# ISA_Sound_Card.net
KiCad netlist of a schematic drawn in EAGLE
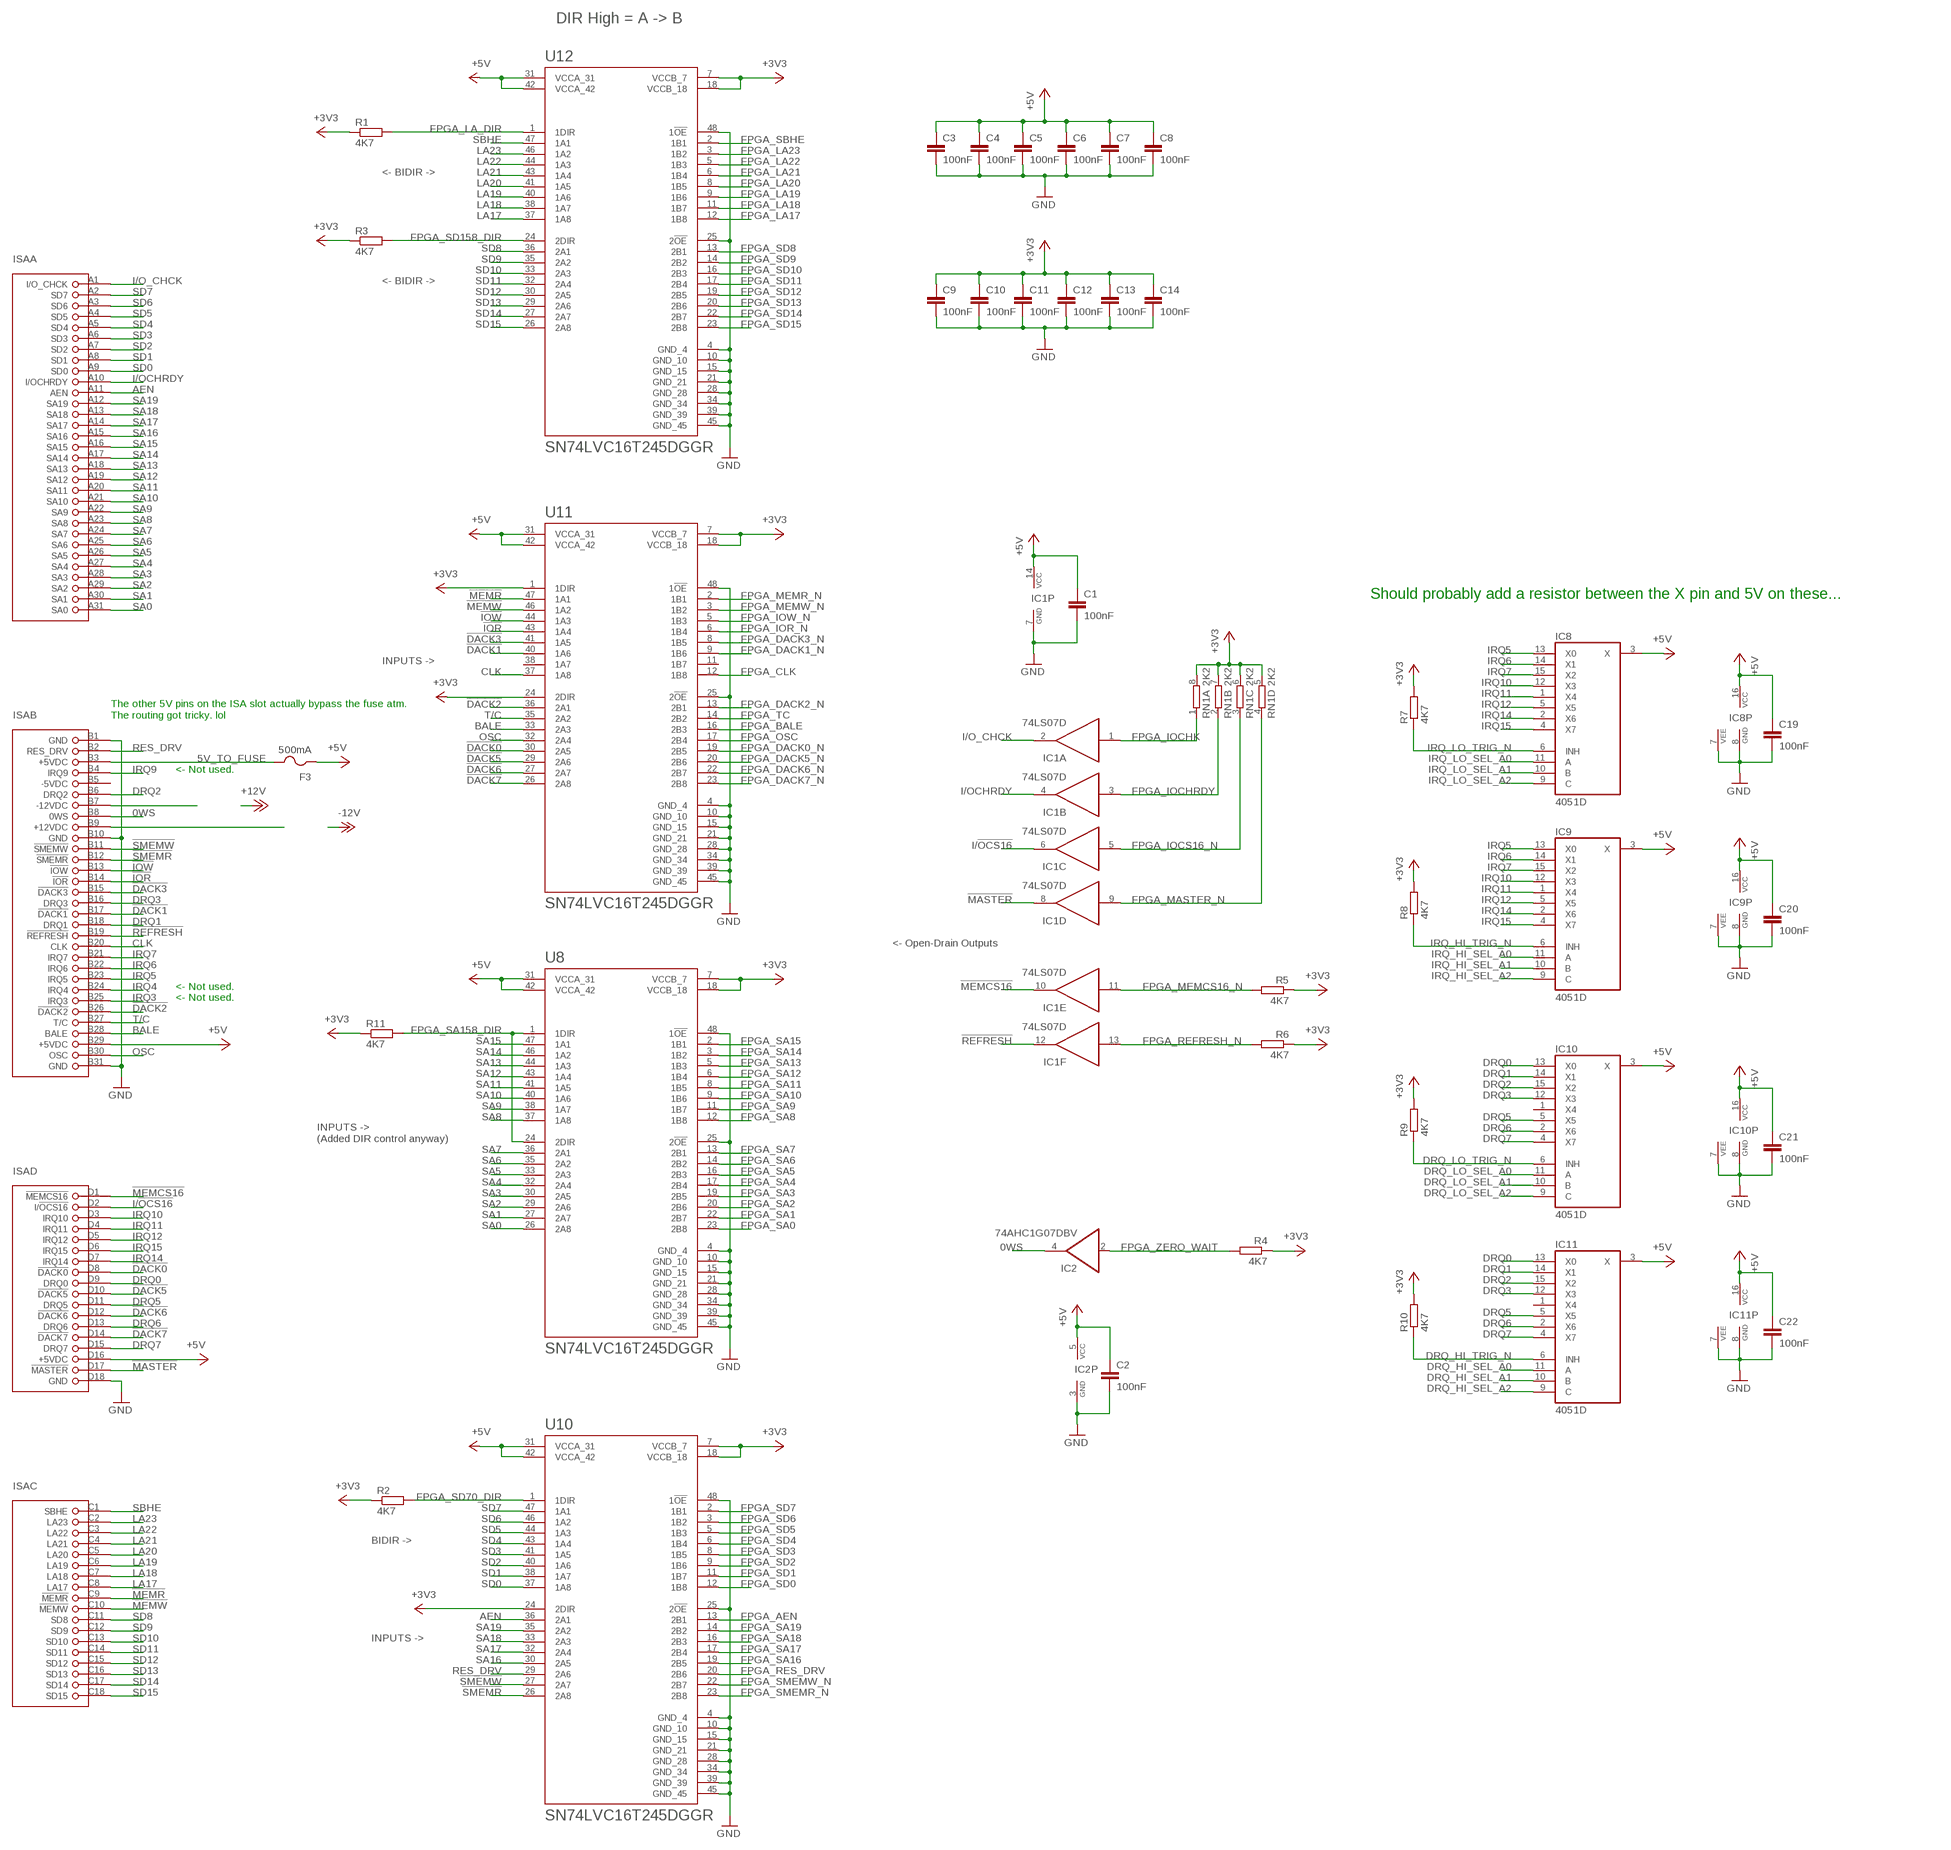
[diagram p0: schematic, sheet 1]
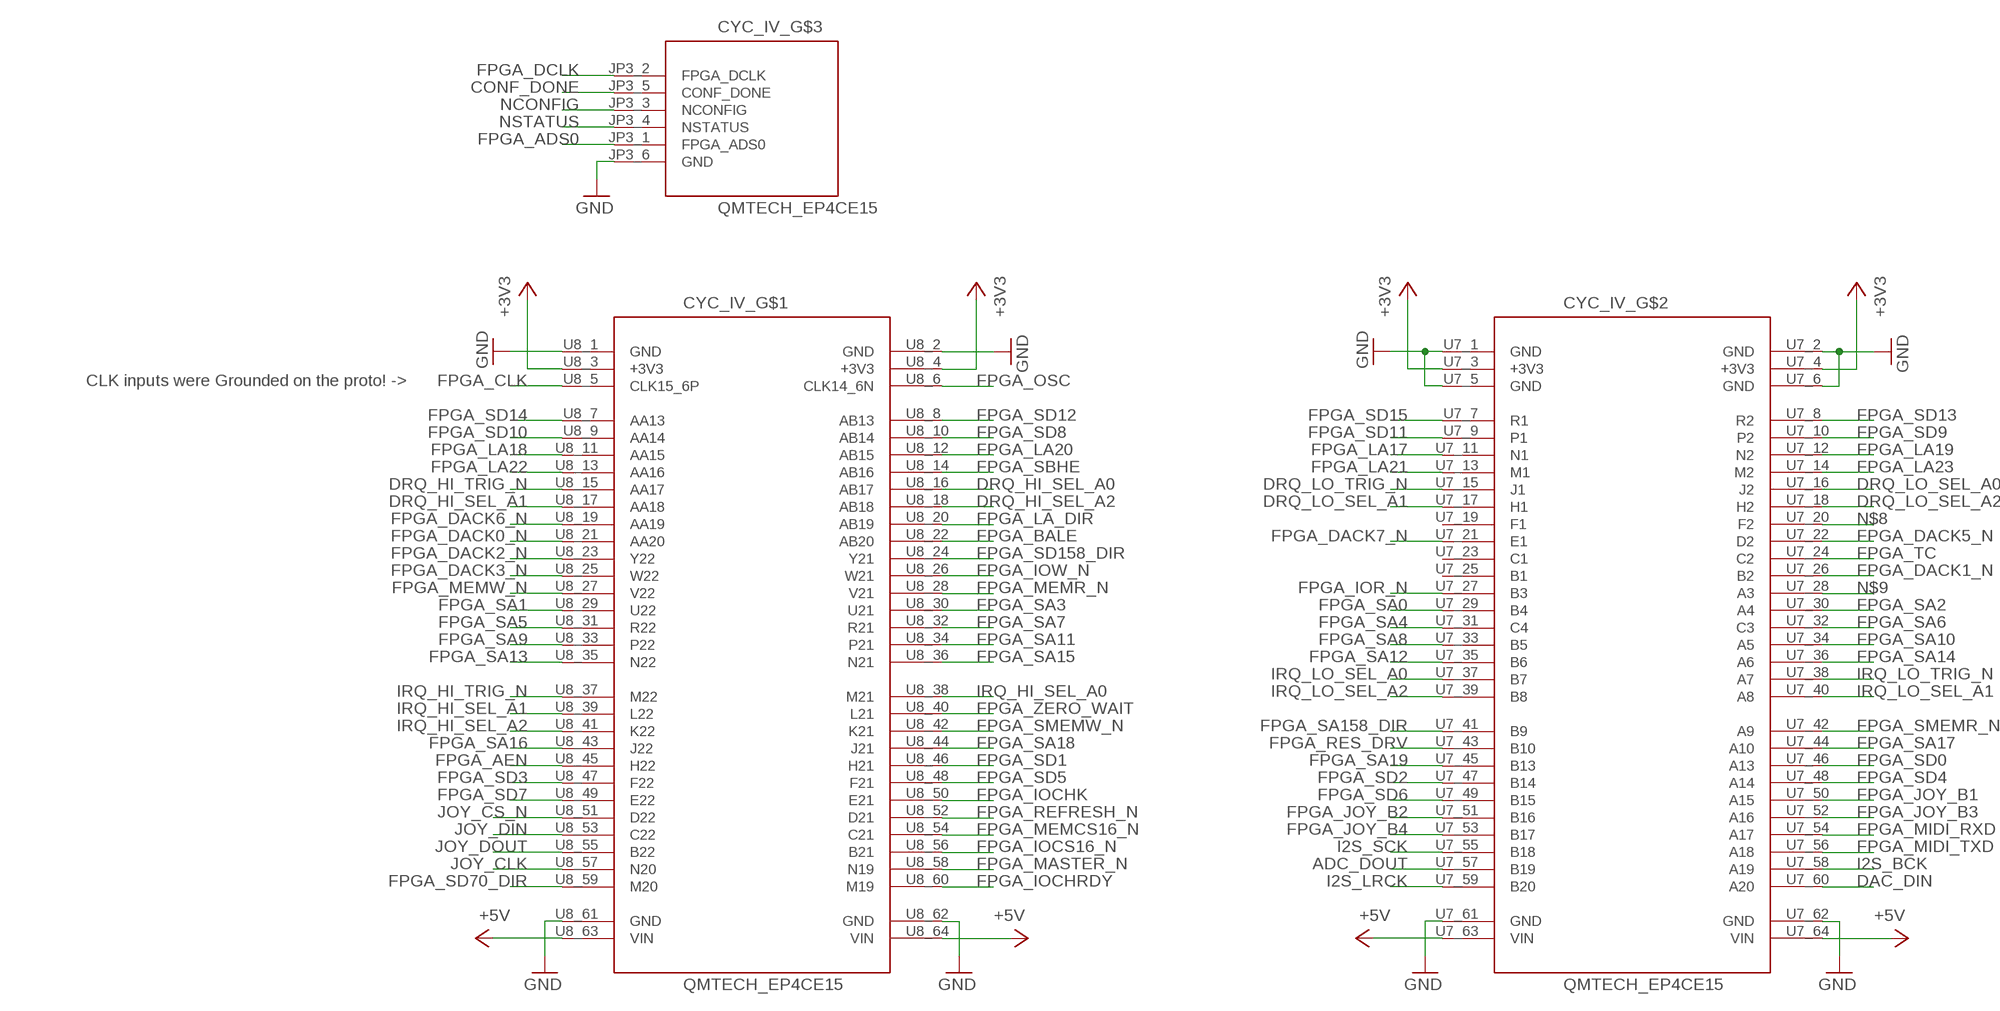
[diagram p1: schematic, sheet 2]
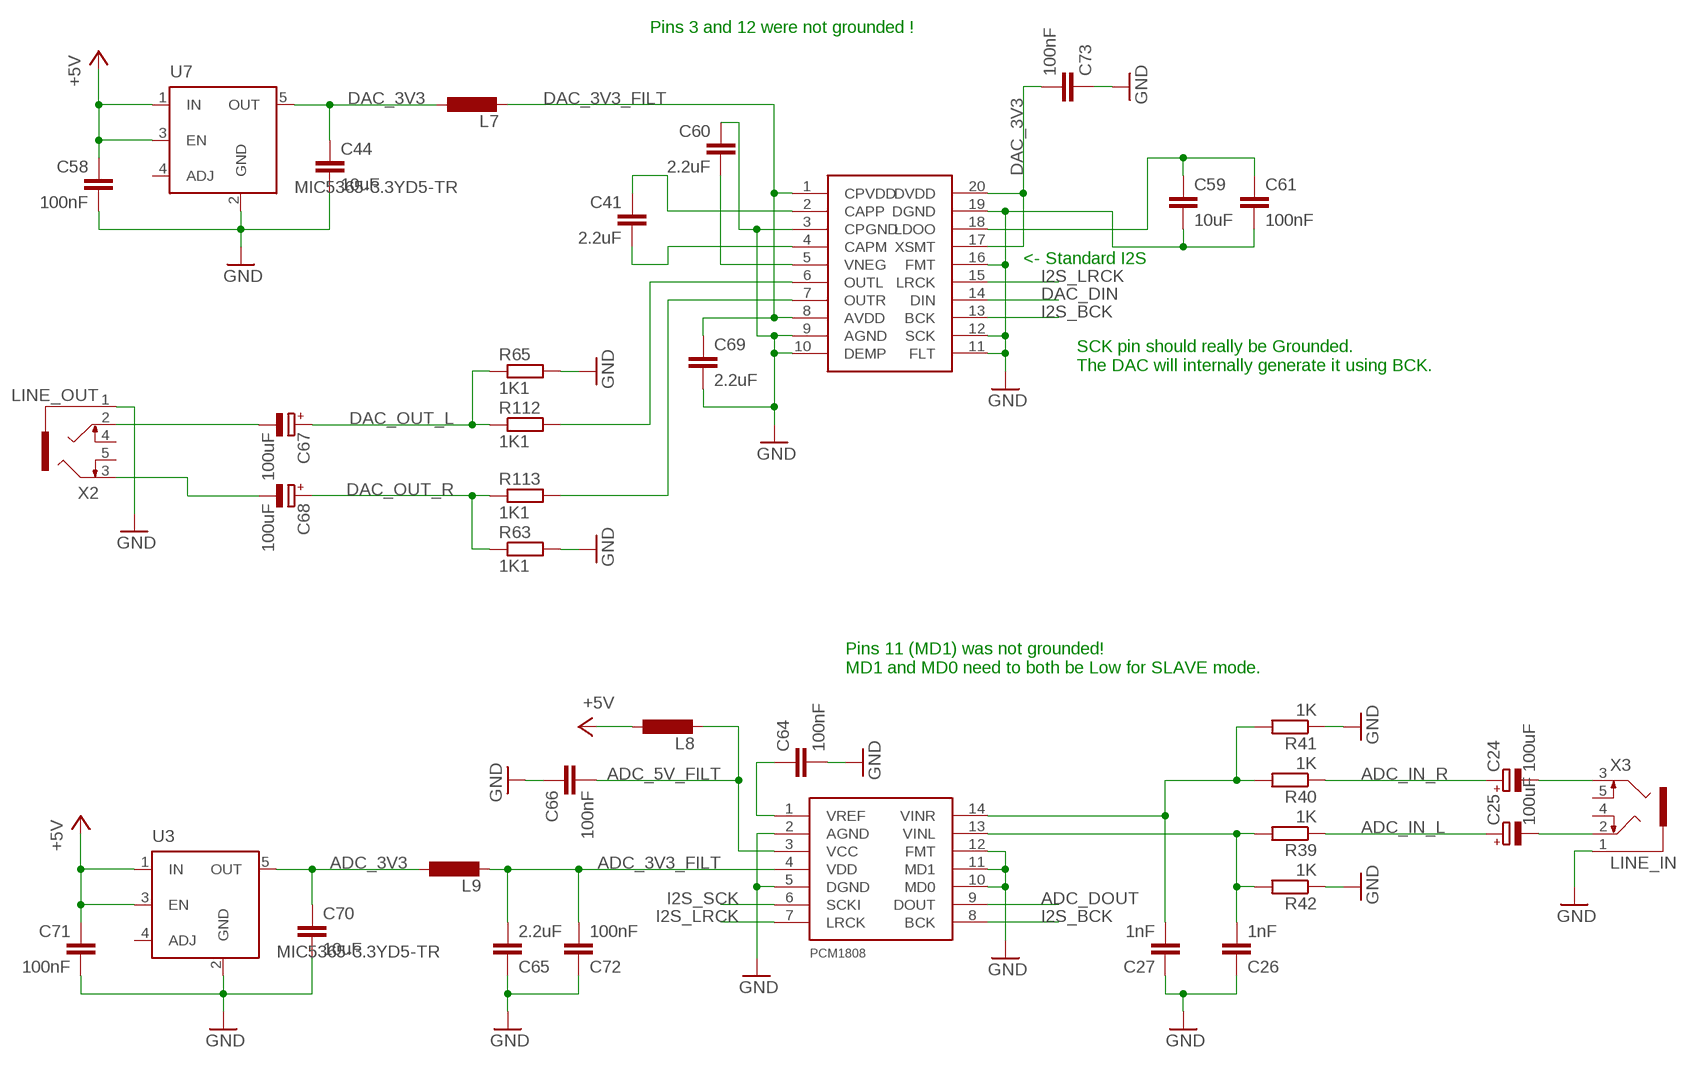
[diagram p2: schematic, sheet 3]
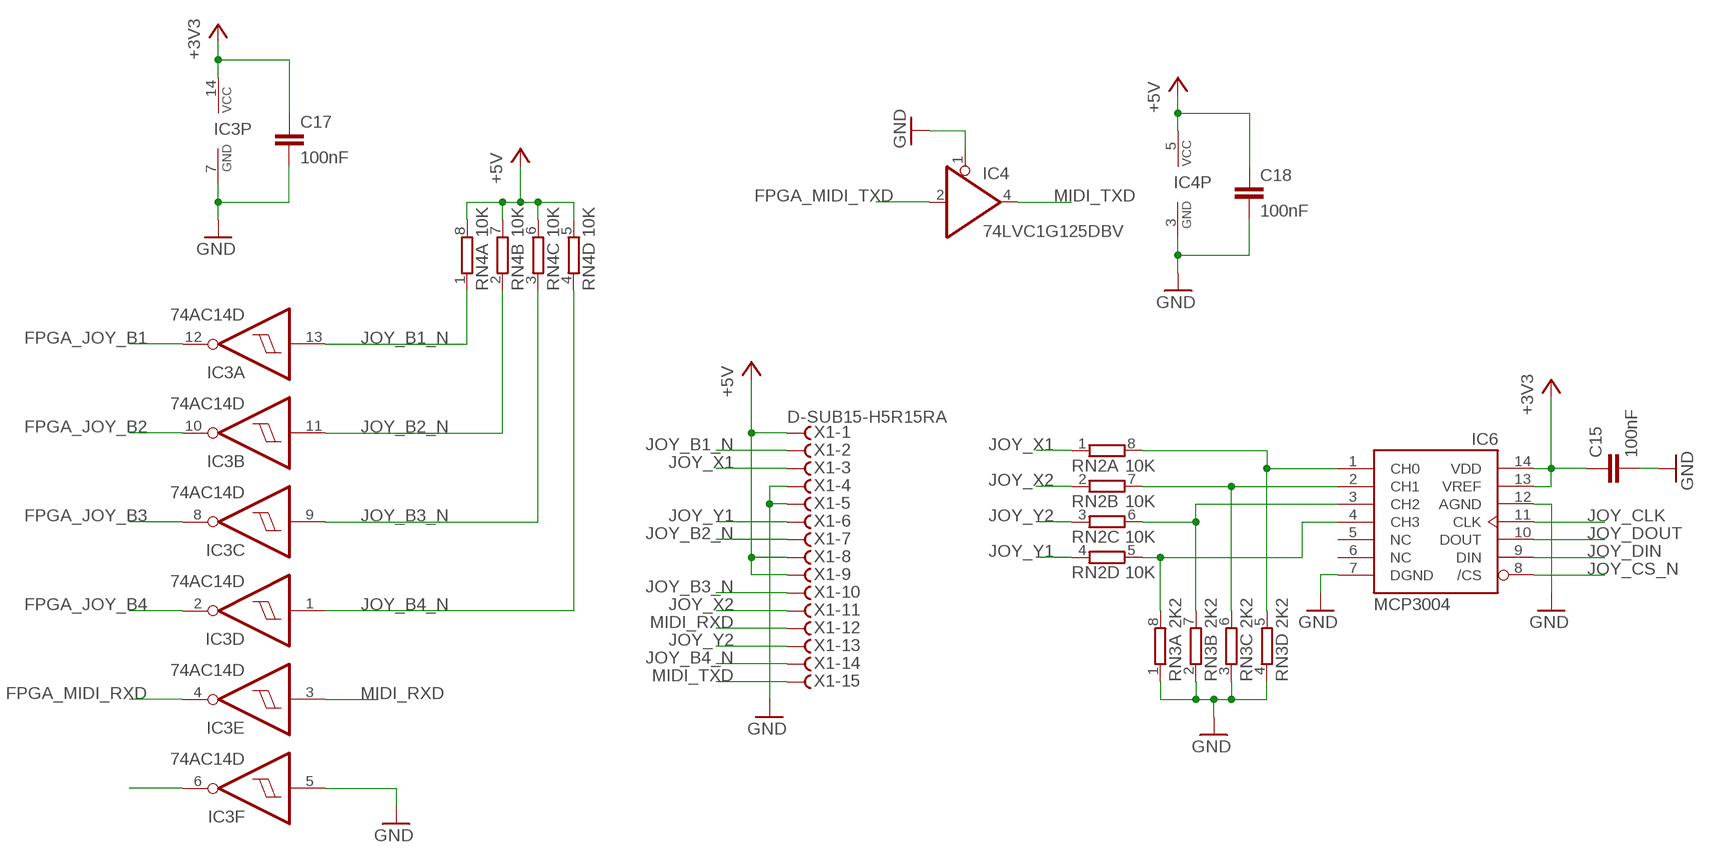
[diagram p3: schematic, sheet 4]

(export (version "E")
  (design (tool "Eeschema 10.0.6"))
  (components
    (comp (ref "C1")
      (value "100nF")
      (footprint "eagle-import:C0603")
      (libsource (lib "eagle-import") (part "C-EUC0603"))
    )
    (comp (ref "C2")
      (value "100nF")
      (footprint "eagle-import:C0603")
      (libsource (lib "eagle-import") (part "C-EUC0603"))
    )
    (comp (ref "C3")
      (value "100nF")
      (footprint "eagle-import:C0603")
      (libsource (lib "eagle-import") (part "C-EUC0603"))
    )
    (comp (ref "C4")
      (value "100nF")
      (footprint "eagle-import:C0603")
      (libsource (lib "eagle-import") (part "C-EUC0603"))
    )
    (comp (ref "C5")
      (value "100nF")
      (footprint "eagle-import:C0603")
      (libsource (lib "eagle-import") (part "C-EUC0603"))
    )
    (comp (ref "C6")
      (value "100nF")
      (footprint "eagle-import:C0603")
      (libsource (lib "eagle-import") (part "C-EUC0603"))
    )
    (comp (ref "C7")
      (value "100nF")
      (footprint "eagle-import:C0603")
      (libsource (lib "eagle-import") (part "C-EUC0603"))
    )
    (comp (ref "C8")
      (value "100nF")
      (footprint "eagle-import:C0603")
      (libsource (lib "eagle-import") (part "C-EUC0603"))
    )
    (comp (ref "C9")
      (value "100nF")
      (footprint "eagle-import:C0603")
      (libsource (lib "eagle-import") (part "C-EUC0603"))
    )
    (comp (ref "C10")
      (value "100nF")
      (footprint "eagle-import:C0603")
      (libsource (lib "eagle-import") (part "C-EUC0603"))
    )
    (comp (ref "C11")
      (value "100nF")
      (footprint "eagle-import:C0603")
      (libsource (lib "eagle-import") (part "C-EUC0603"))
    )
    (comp (ref "C12")
      (value "100nF")
      (footprint "eagle-import:C0603")
      (libsource (lib "eagle-import") (part "C-EUC0603"))
    )
    (comp (ref "C13")
      (value "100nF")
      (footprint "eagle-import:C0603")
      (libsource (lib "eagle-import") (part "C-EUC0603"))
    )
    (comp (ref "C14")
      (value "100nF")
      (footprint "eagle-import:C0603")
      (libsource (lib "eagle-import") (part "C-EUC0603"))
    )
    (comp (ref "C19")
      (value "100nF")
      (footprint "eagle-import:C0603")
      (libsource (lib "eagle-import") (part "C-EUC0603"))
    )
    (comp (ref "C20")
      (value "100nF")
      (footprint "eagle-import:C0603")
      (libsource (lib "eagle-import") (part "C-EUC0603"))
    )
    (comp (ref "C21")
      (value "100nF")
      (footprint "eagle-import:C0603")
      (libsource (lib "eagle-import") (part "C-EUC0603"))
    )
    (comp (ref "C22")
      (value "100nF")
      (footprint "eagle-import:C0603")
      (libsource (lib "eagle-import") (part "C-EUC0603"))
    )
    (comp (ref "F3")
      (value "500mA")
      (footprint "eagle-import:R1206")
      (libsource (lib "eagle-import") (part "PTCFUSE-1206"))
    )
    (comp (ref "IC1")
      (value "74LS07D")
      (footprint "eagle-import:SO14")
      (libsource (lib "eagle-import") (part "7407DLS"))
    )
    (comp (ref "IC2")
      (value "74AHC1G07DBV")
      (footprint "eagle-import:SOT23-5")
      (libsource (lib "eagle-import") (part "741G07DBVAHC"))
    )
    (comp (ref "IC8")
      (value "4051D")
      (footprint "eagle-import:SO16")
      (libsource (lib "eagle-import") (part "4051D"))
    )
    (comp (ref "IC9")
      (value "4051D")
      (footprint "eagle-import:SO16")
      (libsource (lib "eagle-import") (part "4051D"))
    )
    (comp (ref "IC10")
      (value "4051D")
      (footprint "eagle-import:SO16")
      (libsource (lib "eagle-import") (part "4051D"))
    )
    (comp (ref "IC11")
      (value "4051D")
      (footprint "eagle-import:SO16")
      (libsource (lib "eagle-import") (part "4051D"))
    )
    (comp (ref "ISA")
      (value "IBMATBUS")
      (footprint "eagle-import:IBM-AT")
      (libsource (lib "eagle-import") (part "IBMATBUS"))
    )
    (comp (ref "R1")
      (value "4K7")
      (footprint "eagle-import:R0603")
      (libsource (lib "eagle-import") (part "R-EU_R0603"))
    )
    (comp (ref "R2")
      (value "4K7")
      (footprint "eagle-import:R0603")
      (libsource (lib "eagle-import") (part "R-EU_R0603"))
    )
    (comp (ref "R3")
      (value "4K7")
      (footprint "eagle-import:R0603")
      (libsource (lib "eagle-import") (part "R-EU_R0603"))
    )
    (comp (ref "R4")
      (value "4K7")
      (footprint "eagle-import:R0603")
      (libsource (lib "eagle-import") (part "R-EU_R0603"))
    )
    (comp (ref "R5")
      (value "4K7")
      (footprint "eagle-import:R0603")
      (libsource (lib "eagle-import") (part "R-EU_R0603"))
    )
    (comp (ref "R6")
      (value "4K7")
      (footprint "eagle-import:R0603")
      (libsource (lib "eagle-import") (part "R-EU_R0603"))
    )
    (comp (ref "R7")
      (value "4K7")
      (footprint "eagle-import:R0603")
      (libsource (lib "eagle-import") (part "R-EU_R0603"))
    )
    (comp (ref "R8")
      (value "4K7")
      (footprint "eagle-import:R0603")
      (libsource (lib "eagle-import") (part "R-EU_R0603"))
    )
    (comp (ref "R9")
      (value "4K7")
      (footprint "eagle-import:R0603")
      (libsource (lib "eagle-import") (part "R-EU_R0603"))
    )
    (comp (ref "R10")
      (value "4K7")
      (footprint "eagle-import:R0603")
      (libsource (lib "eagle-import") (part "R-EU_R0603"))
    )
    (comp (ref "R11")
      (value "4K7")
      (footprint "eagle-import:R0603")
      (libsource (lib "eagle-import") (part "R-EU_R0603"))
    )
    (comp (ref "RN1")
      (value "2K2")
      (footprint "eagle-import:0603-ARC")
      (libsource (lib "eagle-import") (part "4R-N0603-ARC"))
    )
    (comp (ref "U8")
      (value "SN74LVC16T245DGGR")
      (footprint "eagle-import:SOP50P810X120-48N")
      (fields (field (name "MF") "Texas Instruments"))
      (libsource (lib "eagle-import") (part "SN74LVC16T245DGGR"))
    )
    (comp (ref "U10")
      (value "SN74LVC16T245DGGR")
      (footprint "eagle-import:SOP50P810X120-48N")
      (fields (field (name "MF") "Texas Instruments"))
      (libsource (lib "eagle-import") (part "SN74LVC16T245DGGR"))
    )
    (comp (ref "U11")
      (value "SN74LVC16T245DGGR")
      (footprint "eagle-import:SOP50P810X120-48N")
      (fields (field (name "MF") "Texas Instruments"))
      (libsource (lib "eagle-import") (part "SN74LVC16T245DGGR"))
    )
    (comp (ref "U12")
      (value "SN74LVC16T245DGGR")
      (footprint "eagle-import:SOP50P810X120-48N")
      (fields (field (name "MF") "Texas Instruments"))
      (libsource (lib "eagle-import") (part "SN74LVC16T245DGGR"))
    )
    (comp (ref "C15")
      (value "100nF")
      (footprint "eagle-import:C0805")
      (libsource (lib "eagle-import") (part "C-EUC0805"))
    )
    (comp (ref "C17")
      (value "100nF")
      (footprint "eagle-import:C0805")
      (libsource (lib "eagle-import") (part "C-EUC0805"))
    )
    (comp (ref "C18")
      (value "100nF")
      (footprint "eagle-import:C0805")
      (libsource (lib "eagle-import") (part "C-EUC0805"))
    )
    (comp (ref "IC3")
      (value "74AC14D")
      (footprint "eagle-import:SO14")
      (libsource (lib "eagle-import") (part "7414DAC"))
    )
    (comp (ref "IC4")
      (value "74LVC1G125DBV")
      (footprint "eagle-import:SOT23-5")
      (libsource (lib "eagle-import") (part "741G125DBVLVC"))
    )
    (comp (ref "IC6")
      (value "MCP3004")
      (footprint "eagle-import:SO14")
      (libsource (lib "eagle-import") (part "MCP3004"))
    )
    (comp (ref "RN2")
      (value "10K")
      (footprint "eagle-import:0603-ARC")
      (libsource (lib "eagle-import") (part "4R-N0603-ARC"))
    )
    (comp (ref "RN3")
      (value "2K2")
      (footprint "eagle-import:0603-ARC")
      (libsource (lib "eagle-import") (part "4R-N0603-ARC"))
    )
    (comp (ref "RN4")
      (value "10K")
      (footprint "eagle-import:0603-ARC")
      (libsource (lib "eagle-import") (part "4R-N0603-ARC"))
    )
    (comp (ref "X1")
      (value "D-SUB15-H5R15RA")
      (footprint "eagle-import:H5R15RA")
      (fields (field (name "MF") "TYCO ELECTRONICS") (field (name "MPN") "H5R15RA29B"))
      (libsource (lib "eagle-import") (part "D-SUB15-H5R15RA"))
    )
    (comp (ref "C24")
      (value "100uF")
      (footprint "eagle-import:PANASONIC_C")
      (libsource (lib "eagle-import") (part "CPOL-EUC"))
    )
    (comp (ref "C25")
      (value "100uF")
      (footprint "eagle-import:PANASONIC_C")
      (libsource (lib "eagle-import") (part "CPOL-EUC"))
    )
    (comp (ref "C26")
      (value "1nF")
      (footprint "eagle-import:C0805")
      (libsource (lib "eagle-import") (part "C-EUC0805"))
    )
    (comp (ref "C27")
      (value "1nF")
      (footprint "eagle-import:C0805")
      (libsource (lib "eagle-import") (part "C-EUC0805"))
    )
    (comp (ref "C41")
      (value "2.2uF")
      (footprint "eagle-import:C0603")
      (libsource (lib "eagle-import") (part "C-EUC0603"))
    )
    (comp (ref "C44")
      (value "10uF")
      (footprint "eagle-import:C0603")
      (libsource (lib "eagle-import") (part "C-EUC0603"))
    )
    (comp (ref "C58")
      (value "100nF")
      (footprint "eagle-import:C0603")
      (libsource (lib "eagle-import") (part "C-EUC0603"))
    )
    (comp (ref "C59")
      (value "10uF")
      (footprint "eagle-import:C0603")
      (libsource (lib "eagle-import") (part "C-EUC0603"))
    )
    (comp (ref "C60")
      (value "2.2uF")
      (footprint "eagle-import:C0603")
      (libsource (lib "eagle-import") (part "C-EUC0603"))
    )
    (comp (ref "C61")
      (value "100nF")
      (footprint "eagle-import:C0603")
      (libsource (lib "eagle-import") (part "C-EUC0603"))
    )
    (comp (ref "C64")
      (value "100nF")
      (footprint "eagle-import:C0805")
      (libsource (lib "eagle-import") (part "C-EUC0805"))
    )
    (comp (ref "C65")
      (value "2.2uF")
      (footprint "eagle-import:C0603")
      (libsource (lib "eagle-import") (part "C-EUC0603"))
    )
    (comp (ref "C66")
      (value "100nF")
      (footprint "eagle-import:C0603")
      (libsource (lib "eagle-import") (part "C-EUC0603"))
    )
    (comp (ref "C67")
      (value "100uF")
      (footprint "eagle-import:PANASONIC_C")
      (libsource (lib "eagle-import") (part "CPOL-EUC"))
    )
    (comp (ref "C68")
      (value "100uF")
      (footprint "eagle-import:PANASONIC_C")
      (libsource (lib "eagle-import") (part "CPOL-EUC"))
    )
    (comp (ref "C69")
      (value "2.2uF")
      (footprint "eagle-import:C0603")
      (libsource (lib "eagle-import") (part "C-EUC0603"))
    )
    (comp (ref "C70")
      (value "10uF")
      (footprint "eagle-import:C0603")
      (libsource (lib "eagle-import") (part "C-EUC0603"))
    )
    (comp (ref "C71")
      (value "100nF")
      (footprint "eagle-import:C0603")
      (libsource (lib "eagle-import") (part "C-EUC0603"))
    )
    (comp (ref "C72")
      (value "100nF")
      (footprint "eagle-import:C0603")
      (libsource (lib "eagle-import") (part "C-EUC0603"))
    )
    (comp (ref "C73")
      (value "100nF")
      (footprint "eagle-import:C0603")
      (libsource (lib "eagle-import") (part "C-EUC0603"))
    )
    (comp (ref "L7")
      (value "L-EUL2012C")
      (footprint "eagle-import:L2012C")
      (libsource (lib "eagle-import") (part "L-EUL2012C"))
    )
    (comp (ref "L8")
      (value "L-EUL2012C")
      (footprint "eagle-import:L2012C")
      (libsource (lib "eagle-import") (part "L-EUL2012C"))
    )
    (comp (ref "L9")
      (value "L-EUL2012C")
      (footprint "eagle-import:L2012C")
      (libsource (lib "eagle-import") (part "L-EUL2012C"))
    )
    (comp (ref "R39")
      (value "1K")
      (footprint "eagle-import:R0603")
      (libsource (lib "eagle-import") (part "R-EU_R0603"))
    )
    (comp (ref "R40")
      (value "1K")
      (footprint "eagle-import:R0603")
      (libsource (lib "eagle-import") (part "R-EU_R0603"))
    )
    (comp (ref "R41")
      (value "1K")
      (footprint "eagle-import:R0603")
      (libsource (lib "eagle-import") (part "R-EU_R0603"))
    )
    (comp (ref "R42")
      (value "1K")
      (footprint "eagle-import:R0603")
      (libsource (lib "eagle-import") (part "R-EU_R0603"))
    )
    (comp (ref "R63")
      (value "1K1")
      (footprint "eagle-import:R0603")
      (libsource (lib "eagle-import") (part "R-EU_R0603"))
    )
    (comp (ref "R65")
      (value "1K1")
      (footprint "eagle-import:R0603")
      (libsource (lib "eagle-import") (part "R-EU_R0603"))
    )
    (comp (ref "R112")
      (value "1K1")
      (footprint "eagle-import:R0603")
      (libsource (lib "eagle-import") (part "R-EU_R0603"))
    )
    (comp (ref "R113")
      (value "1K1")
      (footprint "eagle-import:R0603")
      (libsource (lib "eagle-import") (part "R-EU_R0603"))
    )
    (comp (ref "U1")
      (value "PCM1808")
      (footprint "eagle-import:TSSOP14")
      (libsource (lib "eagle-import") (part "PCM1808"))
    )
    (comp (ref "U3")
      (value "MIC5365-3.3YD5-TR")
      (footprint "eagle-import:SOT23-5")
      (fields (field (name "MF") "ALTERA CORPORATION") (field (name "MPN") "MIC5219BM5 TR"))
      (libsource (lib "eagle-import") (part "MIC5219BM5"))
    )
    (comp (ref "U4")
      (value "PCM5102")
      (footprint "eagle-import:TSSOP20")
      (libsource (lib "eagle-import") (part "PCM5102"))
    )
    (comp (ref "U7")
      (value "MIC5365-3.3YD5-TR")
      (footprint "eagle-import:SOT23-5")
      (fields (field (name "MF") "ALTERA CORPORATION") (field (name "MPN") "MIC5219BM5 TR"))
      (libsource (lib "eagle-import") (part "MIC5219BM5"))
    )
    (comp (ref "X2")
      (value "LINE_OUT")
      (footprint "eagle-import:1503_09")
      (libsource (lib "eagle-import") (part "1503_09"))
    )
    (comp (ref "X3")
      (value "LINE_IN")
      (footprint "eagle-import:1503_09")
      (libsource (lib "eagle-import") (part "1503_09"))
    )
    (comp (ref "CYC_IV_")
      (value "QMTECH_EP4CE15")
      (footprint "eagle-import:QMTECH_EP4CE15_SMD")
      (libsource (lib "eagle-import") (part "QMTECH_EP4CE15"))
    )
  )
  (nets
    (net (code "1") (name "+3V3") (class "Default")
      (node (ref "C10") (pin "1") (pinfunction "1_1") (pintype "passive"))
      (node (ref "C11") (pin "1") (pinfunction "1_1") (pintype "passive"))
      (node (ref "C12") (pin "1") (pinfunction "1_1") (pintype "passive"))
      (node (ref "C13") (pin "1") (pinfunction "1_1") (pintype "passive"))
      (node (ref "C14") (pin "1") (pinfunction "1_1") (pintype "passive"))
      (node (ref "C15") (pin "1") (pinfunction "1_1") (pintype "passive"))
      (node (ref "C17") (pin "1") (pinfunction "1_1") (pintype "passive"))
      (node (ref "C9") (pin "1") (pinfunction "1_1") (pintype "passive"))
      (node (ref "CYC_IV_") (pin "U7_3") (pinfunction "+3V3_U7_3") (pintype "power_in"))
      (node (ref "CYC_IV_") (pin "U7_4") (pinfunction "+3V3_U7_4") (pintype "power_in"))
      (node (ref "CYC_IV_") (pin "U8_3") (pinfunction "+3V3_U8_3") (pintype "power_in"))
      (node (ref "CYC_IV_") (pin "U8_4") (pinfunction "+3V3_U8_4") (pintype "power_in"))
      (node (ref "IC3") (pin "14") (pinfunction "VCC_14") (pintype "power_in"))
      (node (ref "IC6") (pin "13") (pinfunction "VREF_13") (pintype "input"))
      (node (ref "IC6") (pin "14") (pinfunction "VDD_14") (pintype "power_in"))
      (node (ref "R1") (pin "1") (pinfunction "1_1") (pintype "passive"))
      (node (ref "R10") (pin "2") (pinfunction "2_2") (pintype "passive"))
      (node (ref "R11") (pin "1") (pinfunction "1_1") (pintype "passive"))
      (node (ref "R2") (pin "1") (pinfunction "1_1") (pintype "passive"))
      (node (ref "R3") (pin "1") (pinfunction "1_1") (pintype "passive"))
      (node (ref "R4") (pin "1") (pinfunction "1_1") (pintype "passive"))
      (node (ref "R5") (pin "1") (pinfunction "1_1") (pintype "passive"))
      (node (ref "R6") (pin "1") (pinfunction "1_1") (pintype "passive"))
      (node (ref "R7") (pin "2") (pinfunction "2_2") (pintype "passive"))
      (node (ref "R8") (pin "2") (pinfunction "2_2") (pintype "passive"))
      (node (ref "R9") (pin "2") (pinfunction "2_2") (pintype "passive"))
      (node (ref "RN1") (pin "5") (pinfunction "2_5") (pintype "passive"))
      (node (ref "RN1") (pin "6") (pinfunction "2_6") (pintype "passive"))
      (node (ref "RN1") (pin "7") (pinfunction "2_7") (pintype "passive"))
      (node (ref "RN1") (pin "8") (pinfunction "2_8") (pintype "passive"))
      (node (ref "U10") (pin "18") (pinfunction "VCCB_18_18") (pintype "power_in"))
      (node (ref "U10") (pin "24") (pinfunction "2DIR_24") (pintype "input"))
      (node (ref "U10") (pin "7") (pinfunction "VCCB_7_7") (pintype "power_in"))
      (node (ref "U11") (pin "1") (pinfunction "1DIR_1") (pintype "input"))
      (node (ref "U11") (pin "18") (pinfunction "VCCB_18_18") (pintype "power_in"))
      (node (ref "U11") (pin "24") (pinfunction "2DIR_24") (pintype "input"))
      (node (ref "U11") (pin "7") (pinfunction "VCCB_7_7") (pintype "power_in"))
      (node (ref "U12") (pin "18") (pinfunction "VCCB_18_18") (pintype "power_in"))
      (node (ref "U12") (pin "7") (pinfunction "VCCB_7_7") (pintype "power_in"))
      (node (ref "U8") (pin "18") (pinfunction "VCCB_18_18") (pintype "power_in"))
      (node (ref "U8") (pin "7") (pinfunction "VCCB_7_7") (pintype "power_in"))
    )
    (net (code "2") (name "+5V") (class "Default")
      (node (ref "C1") (pin "1") (pinfunction "1_1") (pintype "passive"))
      (node (ref "C18") (pin "1") (pinfunction "1_1") (pintype "passive"))
      (node (ref "C19") (pin "1") (pinfunction "1_1") (pintype "passive"))
      (node (ref "C2") (pin "1") (pinfunction "1_1") (pintype "passive"))
      (node (ref "C20") (pin "1") (pinfunction "1_1") (pintype "passive"))
      (node (ref "C21") (pin "1") (pinfunction "1_1") (pintype "passive"))
      (node (ref "C22") (pin "1") (pinfunction "1_1") (pintype "passive"))
      (node (ref "C3") (pin "1") (pinfunction "1_1") (pintype "passive"))
      (node (ref "C4") (pin "1") (pinfunction "1_1") (pintype "passive"))
      (node (ref "C5") (pin "1") (pinfunction "1_1") (pintype "passive"))
      (node (ref "C58") (pin "1") (pinfunction "1_1") (pintype "passive"))
      (node (ref "C6") (pin "1") (pinfunction "1_1") (pintype "passive"))
      (node (ref "C7") (pin "1") (pinfunction "1_1") (pintype "passive"))
      (node (ref "C71") (pin "1") (pinfunction "1_1") (pintype "passive"))
      (node (ref "C8") (pin "1") (pinfunction "1_1") (pintype "passive"))
      (node (ref "CYC_IV_") (pin "U7_63") (pinfunction "VIN_U7_63") (pintype "power_in"))
      (node (ref "CYC_IV_") (pin "U7_64") (pinfunction "VIN_U7_64") (pintype "power_in"))
      (node (ref "CYC_IV_") (pin "U8_63") (pinfunction "VIN_U8_63") (pintype "power_in"))
      (node (ref "CYC_IV_") (pin "U8_64") (pinfunction "VIN_U8_64") (pintype "power_in"))
      (node (ref "F3") (pin "1") (pinfunction "1_1") (pintype "passive"))
      (node (ref "IC1") (pin "14") (pinfunction "VCC_14") (pintype "power_in"))
      (node (ref "IC10") (pin "16") (pinfunction "VCC_16") (pintype "power_in"))
      (node (ref "IC10") (pin "3") (pinfunction "X_3") (pintype "bidirectional"))
      (node (ref "IC11") (pin "16") (pinfunction "VCC_16") (pintype "power_in"))
      (node (ref "IC11") (pin "3") (pinfunction "X_3") (pintype "bidirectional"))
      (node (ref "IC2") (pin "5") (pinfunction "VCC_5") (pintype "power_in"))
      (node (ref "IC4") (pin "5") (pinfunction "VCC_5") (pintype "power_in"))
      (node (ref "IC8") (pin "16") (pinfunction "VCC_16") (pintype "power_in"))
      (node (ref "IC8") (pin "3") (pinfunction "X_3") (pintype "bidirectional"))
      (node (ref "IC9") (pin "16") (pinfunction "VCC_16") (pintype "power_in"))
      (node (ref "IC9") (pin "3") (pinfunction "X_3") (pintype "bidirectional"))
      (node (ref "ISA") (pin "B29") (pinfunction "+5VDC_B29") (pintype "power_in"))
      (node (ref "ISA") (pin "D16") (pinfunction "+5VDC_D16") (pintype "power_in"))
      (node (ref "L8") (pin "1") (pinfunction "1_1") (pintype "passive"))
      (node (ref "RN4") (pin "5") (pinfunction "2_5") (pintype "passive"))
      (node (ref "RN4") (pin "6") (pinfunction "2_6") (pintype "passive"))
      (node (ref "RN4") (pin "7") (pinfunction "2_7") (pintype "passive"))
      (node (ref "RN4") (pin "8") (pinfunction "2_8") (pintype "passive"))
      (node (ref "U10") (pin "31") (pinfunction "VCCA_31_31") (pintype "power_in"))
      (node (ref "U10") (pin "42") (pinfunction "VCCA_42_42") (pintype "power_in"))
      (node (ref "U11") (pin "31") (pinfunction "VCCA_31_31") (pintype "power_in"))
      (node (ref "U11") (pin "42") (pinfunction "VCCA_42_42") (pintype "power_in"))
      (node (ref "U12") (pin "31") (pinfunction "VCCA_31_31") (pintype "power_in"))
      (node (ref "U12") (pin "42") (pinfunction "VCCA_42_42") (pintype "power_in"))
      (node (ref "U3") (pin "1") (pinfunction "IN_1") (pintype "input"))
      (node (ref "U3") (pin "3") (pinfunction "EN_3") (pintype "input"))
      (node (ref "U7") (pin "1") (pinfunction "IN_1") (pintype "input"))
      (node (ref "U7") (pin "3") (pinfunction "EN_3") (pintype "input"))
      (node (ref "U8") (pin "31") (pinfunction "VCCA_31_31") (pintype "power_in"))
      (node (ref "U8") (pin "42") (pinfunction "VCCA_42_42") (pintype "power_in"))
      (node (ref "X1") (pin "1") (pinfunction "F_1") (pintype "passive"))
      (node (ref "X1") (pin "8") (pinfunction "F_8") (pintype "passive"))
      (node (ref "X1") (pin "9") (pinfunction "F_9") (pintype "passive"))
    )
    (net (code "4") (name "-5VDC") (class "Default")
      (node (ref "ISA") (pin "B5") (pinfunction "-5VDC_B5") (pintype "power_in"))
    )
    (net (code "6") (name "0WS") (class "Default")
      (node (ref "IC2") (pin "4") (pinfunction "O_4") (pintype "open_collector"))
      (node (ref "ISA") (pin "B8") (pinfunction "0WS_B8") (pintype "input"))
    )
    (net (code "7") (name "5V_TO_FUSE") (class "Default")
      (node (ref "F3") (pin "2") (pinfunction "2_2") (pintype "passive"))
      (node (ref "ISA") (pin "B3") (pinfunction "+5VDC_B3") (pintype "power_in"))
    )
    (net (code "8") (name "ADC_3V3") (class "Default")
      (node (ref "C70") (pin "1") (pinfunction "1_1") (pintype "passive"))
      (node (ref "L9") (pin "1") (pinfunction "1_1") (pintype "passive"))
      (node (ref "U3") (pin "5") (pinfunction "OUT_5") (pintype "output"))
    )
    (net (code "9") (name "ADC_3V3_FILT") (class "Default")
      (node (ref "C65") (pin "2") (pinfunction "2_2") (pintype "passive"))
      (node (ref "C72") (pin "2") (pinfunction "2_2") (pintype "passive"))
      (node (ref "L9") (pin "2") (pinfunction "2_2") (pintype "passive"))
      (node (ref "U1") (pin "4") (pinfunction "VDD_4") (pintype "bidirectional"))
    )
    (net (code "10") (name "ADC_5V_FILT") (class "Default")
      (node (ref "C66") (pin "2") (pinfunction "2_2") (pintype "passive"))
      (node (ref "L8") (pin "2") (pinfunction "2_2") (pintype "passive"))
      (node (ref "U1") (pin "3") (pinfunction "VCC_3") (pintype "bidirectional"))
    )
    (net (code "11") (name "ADC_DOUT") (class "Default")
      (node (ref "CYC_IV_") (pin "U7_57") (pinfunction "B19_U7_57") (pintype "bidirectional"))
      (node (ref "U1") (pin "9") (pinfunction "DOUT_9") (pintype "bidirectional"))
    )
    (net (code "12") (name "ADC_IN_L") (class "Default")
      (node (ref "C25") (pin "+") (pinfunction "+_+") (pintype "passive"))
      (node (ref "R39") (pin "1") (pinfunction "1_1") (pintype "passive"))
    )
    (net (code "13") (name "ADC_IN_R") (class "Default")
      (node (ref "C24") (pin "+") (pinfunction "+_+") (pintype "passive"))
      (node (ref "R40") (pin "1") (pinfunction "1_1") (pintype "passive"))
    )
    (net (code "14") (name "AEN") (class "Default")
      (node (ref "ISA") (pin "A11") (pinfunction "AEN_A11") (pintype "output"))
      (node (ref "U10") (pin "36") (pinfunction "2A1_36") (pintype "bidirectional"))
    )
    (net (code "15") (name "BALE") (class "Default")
      (node (ref "ISA") (pin "B28") (pinfunction "BALE_B28") (pintype "output"))
      (node (ref "U11") (pin "33") (pinfunction "2A3_33") (pintype "bidirectional"))
    )
    (net (code "16") (name "CLK") (class "Default")
      (node (ref "ISA") (pin "B20") (pinfunction "CLK_B20") (pintype "output"))
      (node (ref "U11") (pin "37") (pinfunction "1A8_37") (pintype "bidirectional"))
    )
    (net (code "17") (name "CONF_DONE") (class "Default")
      (node (ref "CYC_IV_") (pin "JP3_5") (pinfunction "CONF_DONE_JP3_5") (pintype "output"))
    )
    (net (code "18") (name "DAC_3V3") (class "Default")
      (node (ref "C44") (pin "1") (pinfunction "1_1") (pintype "passive"))
      (node (ref "C73") (pin "2") (pinfunction "2_2") (pintype "passive"))
      (node (ref "L7") (pin "1") (pinfunction "1_1") (pintype "passive"))
      (node (ref "U4") (pin "17") (pinfunction "XSMT_17") (pintype "bidirectional"))
      (node (ref "U4") (pin "20") (pinfunction "DVDD_20") (pintype "bidirectional"))
      (node (ref "U7") (pin "5") (pinfunction "OUT_5") (pintype "output"))
    )
    (net (code "19") (name "DAC_3V3_FILT") (class "Default")
      (node (ref "C69") (pin "1") (pinfunction "1_1") (pintype "passive"))
      (node (ref "L7") (pin "2") (pinfunction "2_2") (pintype "passive"))
      (node (ref "U4") (pin "1") (pinfunction "CPVDD_1") (pintype "bidirectional"))
      (node (ref "U4") (pin "8") (pinfunction "AVDD_8") (pintype "bidirectional"))
    )
    (net (code "20") (name "DAC_DIN") (class "Default")
      (node (ref "CYC_IV_") (pin "U7_60") (pinfunction "A20_U7_60") (pintype "bidirectional"))
      (node (ref "U4") (pin "14") (pinfunction "DIN_14") (pintype "bidirectional"))
    )
    (net (code "21") (name "DAC_OUT_L") (class "Default")
      (node (ref "C67") (pin "+") (pinfunction "+_+") (pintype "passive"))
      (node (ref "R112") (pin "1") (pinfunction "1_1") (pintype "passive"))
      (node (ref "R65") (pin "1") (pinfunction "1_1") (pintype "passive"))
    )
    (net (code "22") (name "DAC_OUT_R") (class "Default")
      (node (ref "C68") (pin "+") (pinfunction "+_+") (pintype "passive"))
      (node (ref "R113") (pin "1") (pinfunction "1_1") (pintype "passive"))
      (node (ref "R63") (pin "1") (pinfunction "1_1") (pintype "passive"))
    )
    (net (code "23") (name "DRQ0") (class "Default")
      (node (ref "IC10") (pin "13") (pinfunction "X0_13") (pintype "bidirectional"))
      (node (ref "IC11") (pin "13") (pinfunction "X0_13") (pintype "bidirectional"))
      (node (ref "ISA") (pin "D9") (pinfunction "DRQ0_D9") (pintype "input"))
    )
    (net (code "24") (name "DRQ1") (class "Default")
      (node (ref "IC10") (pin "14") (pinfunction "X1_14") (pintype "bidirectional"))
      (node (ref "IC11") (pin "14") (pinfunction "X1_14") (pintype "bidirectional"))
      (node (ref "ISA") (pin "B18") (pinfunction "DRQ1_B18") (pintype "input"))
    )
    (net (code "25") (name "DRQ2") (class "Default")
      (node (ref "IC10") (pin "15") (pinfunction "X2_15") (pintype "bidirectional"))
      (node (ref "IC11") (pin "15") (pinfunction "X2_15") (pintype "bidirectional"))
      (node (ref "ISA") (pin "B6") (pinfunction "DRQ2_B6") (pintype "input"))
    )
    (net (code "26") (name "DRQ3") (class "Default")
      (node (ref "IC10") (pin "12") (pinfunction "X3_12") (pintype "bidirectional"))
      (node (ref "IC11") (pin "12") (pinfunction "X3_12") (pintype "bidirectional"))
      (node (ref "ISA") (pin "B16") (pinfunction "DRQ3_B16") (pintype "input"))
    )
    (net (code "27") (name "DRQ5") (class "Default")
      (node (ref "IC10") (pin "5") (pinfunction "X5_5") (pintype "bidirectional"))
      (node (ref "IC11") (pin "5") (pinfunction "X5_5") (pintype "bidirectional"))
      (node (ref "ISA") (pin "D11") (pinfunction "DRQ5_D11") (pintype "input"))
    )
    (net (code "28") (name "DRQ6") (class "Default")
      (node (ref "IC10") (pin "2") (pinfunction "X6_2") (pintype "bidirectional"))
      (node (ref "IC11") (pin "2") (pinfunction "X6_2") (pintype "bidirectional"))
      (node (ref "ISA") (pin "D13") (pinfunction "DRQ6_D13") (pintype "input"))
    )
    (net (code "29") (name "DRQ7") (class "Default")
      (node (ref "IC10") (pin "4") (pinfunction "X7_4") (pintype "bidirectional"))
      (node (ref "IC11") (pin "4") (pinfunction "X7_4") (pintype "bidirectional"))
      (node (ref "ISA") (pin "D15") (pinfunction "DRQ7_D15") (pintype "input"))
    )
    (net (code "30") (name "DRQ_HI_SEL_A0") (class "Default")
      (node (ref "CYC_IV_") (pin "U8_16") (pinfunction "AB17_U8_16") (pintype "bidirectional"))
      (node (ref "IC11") (pin "11") (pinfunction "A_11") (pintype "input"))
    )
    (net (code "31") (name "DRQ_HI_SEL_A1") (class "Default")
      (node (ref "CYC_IV_") (pin "U8_17") (pinfunction "AA18_U8_17") (pintype "bidirectional"))
      (node (ref "IC11") (pin "10") (pinfunction "B_10") (pintype "input"))
    )
    (net (code "32") (name "DRQ_HI_SEL_A2") (class "Default")
      (node (ref "CYC_IV_") (pin "U8_18") (pinfunction "AB18_U8_18") (pintype "bidirectional"))
      (node (ref "IC11") (pin "9") (pinfunction "C_9") (pintype "input"))
    )
    (net (code "33") (name "DRQ_HI_TRIG_N") (class "Default")
      (node (ref "CYC_IV_") (pin "U8_15") (pinfunction "AA17_U8_15") (pintype "bidirectional"))
      (node (ref "IC11") (pin "6") (pinfunction "INH_6") (pintype "input"))
      (node (ref "R10") (pin "1") (pinfunction "1_1") (pintype "passive"))
    )
    (net (code "34") (name "DRQ_LO_SEL_A0") (class "Default")
      (node (ref "CYC_IV_") (pin "U7_16") (pinfunction "J2_U7_16") (pintype "bidirectional"))
      (node (ref "IC10") (pin "11") (pinfunction "A_11") (pintype "input"))
    )
    (net (code "35") (name "DRQ_LO_SEL_A1") (class "Default")
      (node (ref "CYC_IV_") (pin "U7_17") (pinfunction "H1_U7_17") (pintype "bidirectional"))
      (node (ref "IC10") (pin "10") (pinfunction "B_10") (pintype "input"))
    )
    (net (code "36") (name "DRQ_LO_SEL_A2") (class "Default")
      (node (ref "CYC_IV_") (pin "U7_18") (pinfunction "H2_U7_18") (pintype "bidirectional"))
      (node (ref "IC10") (pin "9") (pinfunction "C_9") (pintype "input"))
    )
    (net (code "37") (name "DRQ_LO_TRIG_N") (class "Default")
      (node (ref "CYC_IV_") (pin "U7_15") (pinfunction "J1_U7_15") (pintype "bidirectional"))
      (node (ref "IC10") (pin "6") (pinfunction "INH_6") (pintype "input"))
      (node (ref "R9") (pin "1") (pinfunction "1_1") (pintype "passive"))
    )
    (net (code "38") (name "FPGA_ADS0") (class "Default")
      (node (ref "CYC_IV_") (pin "JP3_1") (pinfunction "FPGA_ADS0_JP3_1") (pintype "bidirectional"))
    )
    (net (code "39") (name "FPGA_AEN") (class "Default")
      (node (ref "CYC_IV_") (pin "U8_45") (pinfunction "H22_U8_45") (pintype "bidirectional"))
      (node (ref "U10") (pin "13") (pinfunction "2B1_13") (pintype "bidirectional"))
    )
    (net (code "40") (name "FPGA_BALE") (class "Default")
      (node (ref "CYC_IV_") (pin "U8_22") (pinfunction "AB20_U8_22") (pintype "bidirectional"))
      (node (ref "U11") (pin "16") (pinfunction "2B3_16") (pintype "bidirectional"))
    )
    (net (code "41") (name "FPGA_CLK") (class "Default")
      (node (ref "CYC_IV_") (pin "U8_5") (pinfunction "CLK15_6P_U8_5") (pintype "power_in"))
      (node (ref "U11") (pin "12") (pinfunction "1B8_12") (pintype "bidirectional"))
    )
    (net (code "42") (name "FPGA_DACK0_N") (class "Default")
      (node (ref "CYC_IV_") (pin "U8_21") (pinfunction "AA20_U8_21") (pintype "bidirectional"))
      (node (ref "U11") (pin "19") (pinfunction "2B5_19") (pintype "bidirectional"))
    )
    (net (code "43") (name "FPGA_DACK1_N") (class "Default")
      (node (ref "CYC_IV_") (pin "U7_26") (pinfunction "B2_U7_26") (pintype "bidirectional"))
      (node (ref "U11") (pin "9") (pinfunction "1B6_9") (pintype "bidirectional"))
    )
    (net (code "44") (name "FPGA_DACK2_N") (class "Default")
      (node (ref "CYC_IV_") (pin "U8_23") (pinfunction "Y22_U8_23") (pintype "bidirectional"))
      (node (ref "U11") (pin "13") (pinfunction "2B1_13") (pintype "bidirectional"))
    )
    (net (code "45") (name "FPGA_DACK3_N") (class "Default")
      (node (ref "CYC_IV_") (pin "U8_25") (pinfunction "W22_U8_25") (pintype "bidirectional"))
      (node (ref "U11") (pin "8") (pinfunction "1B5_8") (pintype "bidirectional"))
    )
    (net (code "46") (name "FPGA_DACK5_N") (class "Default")
      (node (ref "CYC_IV_") (pin "U7_22") (pinfunction "D2_U7_22") (pintype "bidirectional"))
      (node (ref "U11") (pin "20") (pinfunction "2B6_20") (pintype "bidirectional"))
    )
    (net (code "47") (name "FPGA_DACK6_N") (class "Default")
      (node (ref "CYC_IV_") (pin "U8_19") (pinfunction "AA19_U8_19") (pintype "bidirectional"))
      (node (ref "U11") (pin "22") (pinfunction "2B7_22") (pintype "bidirectional"))
    )
    (net (code "48") (name "FPGA_DACK7_N") (class "Default")
      (node (ref "CYC_IV_") (pin "U7_21") (pinfunction "E1_U7_21") (pintype "bidirectional"))
      (node (ref "U11") (pin "23") (pinfunction "2B8_23") (pintype "bidirectional"))
    )
    (net (code "49") (name "FPGA_DCLK") (class "Default")
      (node (ref "CYC_IV_") (pin "JP3_2") (pinfunction "FPGA_DCLK_JP3_2") (pintype "input"))
    )
    (net (code "50") (name "FPGA_IOCHK") (class "Default")
      (node (ref "CYC_IV_") (pin "U8_50") (pinfunction "E21_U8_50") (pintype "bidirectional"))
      (node (ref "IC1") (pin "1") (pinfunction "I_1") (pintype "input"))
      (node (ref "RN1") (pin "1") (pinfunction "1_1") (pintype "passive"))
    )
    (net (code "51") (name "FPGA_IOCHRDY") (class "Default")
      (node (ref "CYC_IV_") (pin "U8_60") (pinfunction "M19_U8_60") (pintype "bidirectional"))
      (node (ref "IC1") (pin "3") (pinfunction "I_3") (pintype "input"))
      (node (ref "RN1") (pin "2") (pinfunction "1_2") (pintype "passive"))
    )
    (net (code "52") (name "FPGA_IOCS16_N") (class "Default")
      (node (ref "CYC_IV_") (pin "U8_56") (pinfunction "B21_U8_56") (pintype "bidirectional"))
      (node (ref "IC1") (pin "5") (pinfunction "I_5") (pintype "input"))
      (node (ref "RN1") (pin "3") (pinfunction "1_3") (pintype "passive"))
    )
    (net (code "53") (name "FPGA_IOR_N") (class "Default")
      (node (ref "CYC_IV_") (pin "U7_27") (pinfunction "B3_U7_27") (pintype "bidirectional"))
      (node (ref "U11") (pin "6") (pinfunction "1B4_6") (pintype "bidirectional"))
    )
    (net (code "54") (name "FPGA_IOW_N") (class "Default")
      (node (ref "CYC_IV_") (pin "U8_26") (pinfunction "W21_U8_26") (pintype "bidirectional"))
      (node (ref "U11") (pin "5") (pinfunction "1B3_5") (pintype "bidirectional"))
    )
    (net (code "55") (name "FPGA_JOY_B1") (class "Default")
      (node (ref "CYC_IV_") (pin "U7_50") (pinfunction "A15_U7_50") (pintype "bidirectional"))
      (node (ref "IC3") (pin "12") (pinfunction "O_12") (pintype "output"))
    )
    (net (code "56") (name "FPGA_JOY_B2") (class "Default")
      (node (ref "CYC_IV_") (pin "U7_51") (pinfunction "B16_U7_51") (pintype "bidirectional"))
      (node (ref "IC3") (pin "10") (pinfunction "O_10") (pintype "output"))
    )
    (net (code "57") (name "FPGA_JOY_B3") (class "Default")
      (node (ref "CYC_IV_") (pin "U7_52") (pinfunction "A16_U7_52") (pintype "bidirectional"))
      (node (ref "IC3") (pin "8") (pinfunction "O_8") (pintype "output"))
    )
    (net (code "58") (name "FPGA_JOY_B4") (class "Default")
      (node (ref "CYC_IV_") (pin "U7_53") (pinfunction "B17_U7_53") (pintype "bidirectional"))
      (node (ref "IC3") (pin "2") (pinfunction "O_2") (pintype "output"))
    )
    (net (code "59") (name "FPGA_LA17") (class "Default")
      (node (ref "CYC_IV_") (pin "U7_11") (pinfunction "N1_U7_11") (pintype "bidirectional"))
      (node (ref "U12") (pin "12") (pinfunction "1B8_12") (pintype "bidirectional"))
    )
    (net (code "60") (name "FPGA_LA18") (class "Default")
      (node (ref "CYC_IV_") (pin "U8_11") (pinfunction "AA15_U8_11") (pintype "bidirectional"))
      (node (ref "U12") (pin "11") (pinfunction "1B7_11") (pintype "bidirectional"))
    )
    (net (code "61") (name "FPGA_LA19") (class "Default")
      (node (ref "CYC_IV_") (pin "U7_12") (pinfunction "N2_U7_12") (pintype "bidirectional"))
      (node (ref "U12") (pin "9") (pinfunction "1B6_9") (pintype "bidirectional"))
    )
    (net (code "62") (name "FPGA_LA20") (class "Default")
      (node (ref "CYC_IV_") (pin "U8_12") (pinfunction "AB15_U8_12") (pintype "bidirectional"))
      (node (ref "U12") (pin "8") (pinfunction "1B5_8") (pintype "bidirectional"))
    )
    (net (code "63") (name "FPGA_LA21") (class "Default")
      (node (ref "CYC_IV_") (pin "U7_13") (pinfunction "M1_U7_13") (pintype "bidirectional"))
      (node (ref "U12") (pin "6") (pinfunction "1B4_6") (pintype "bidirectional"))
    )
    (net (code "64") (name "FPGA_LA22") (class "Default")
      (node (ref "CYC_IV_") (pin "U8_13") (pinfunction "AA16_U8_13") (pintype "bidirectional"))
      (node (ref "U12") (pin "5") (pinfunction "1B3_5") (pintype "bidirectional"))
    )
    (net (code "65") (name "FPGA_LA23") (class "Default")
      (node (ref "CYC_IV_") (pin "U7_14") (pinfunction "M2_U7_14") (pintype "bidirectional"))
      (node (ref "U12") (pin "3") (pinfunction "1B2_3") (pintype "bidirectional"))
    )
    (net (code "66") (name "FPGA_LA_DIR") (class "Default")
      (node (ref "CYC_IV_") (pin "U8_20") (pinfunction "AB19_U8_20") (pintype "bidirectional"))
      (node (ref "R1") (pin "2") (pinfunction "2_2") (pintype "passive"))
      (node (ref "U12") (pin "1") (pinfunction "1DIR_1") (pintype "input"))
    )
    (net (code "67") (name "FPGA_MASTER_N") (class "Default")
      (node (ref "CYC_IV_") (pin "U8_58") (pinfunction "N19_U8_58") (pintype "bidirectional"))
      (node (ref "IC1") (pin "9") (pinfunction "I_9") (pintype "input"))
      (node (ref "RN1") (pin "4") (pinfunction "1_4") (pintype "passive"))
    )
    (net (code "68") (name "FPGA_MEMCS16_N") (class "Default")
      (node (ref "CYC_IV_") (pin "U8_54") (pinfunction "C21_U8_54") (pintype "bidirectional"))
      (node (ref "IC1") (pin "11") (pinfunction "I_11") (pintype "input"))
      (node (ref "R5") (pin "2") (pinfunction "2_2") (pintype "passive"))
    )
    (net (code "69") (name "FPGA_MEMR_N") (class "Default")
      (node (ref "CYC_IV_") (pin "U8_28") (pinfunction "V21_U8_28") (pintype "bidirectional"))
      (node (ref "U11") (pin "2") (pinfunction "1B1_2") (pintype "bidirectional"))
    )
    (net (code "70") (name "FPGA_MEMW_N") (class "Default")
      (node (ref "CYC_IV_") (pin "U8_27") (pinfunction "V22_U8_27") (pintype "bidirectional"))
      (node (ref "U11") (pin "3") (pinfunction "1B2_3") (pintype "bidirectional"))
    )
    (net (code "71") (name "FPGA_MIDI_RXD") (class "Default")
      (node (ref "CYC_IV_") (pin "U7_54") (pinfunction "A17_U7_54") (pintype "bidirectional"))
      (node (ref "IC3") (pin "4") (pinfunction "O_4") (pintype "output"))
    )
    (net (code "72") (name "FPGA_MIDI_TXD") (class "Default")
      (node (ref "CYC_IV_") (pin "U7_56") (pinfunction "A18_U7_56") (pintype "bidirectional"))
      (node (ref "IC4") (pin "2") (pinfunction "I_2") (pintype "input"))
    )
    (net (code "73") (name "FPGA_OSC") (class "Default")
      (node (ref "CYC_IV_") (pin "U8_6") (pinfunction "CLK14_6N_U8_6") (pintype "power_in"))
      (node (ref "U11") (pin "17") (pinfunction "2B4_17") (pintype "bidirectional"))
    )
    (net (code "74") (name "FPGA_REFRESH_N") (class "Default")
      (node (ref "CYC_IV_") (pin "U8_52") (pinfunction "D21_U8_52") (pintype "bidirectional"))
      (node (ref "IC1") (pin "13") (pinfunction "I_13") (pintype "input"))
      (node (ref "R6") (pin "2") (pinfunction "2_2") (pintype "passive"))
    )
    (net (code "75") (name "FPGA_RES_DRV") (class "Default")
      (node (ref "CYC_IV_") (pin "U7_43") (pinfunction "B10_U7_43") (pintype "bidirectional"))
      (node (ref "U10") (pin "20") (pinfunction "2B6_20") (pintype "bidirectional"))
    )
    (net (code "76") (name "FPGA_SA0") (class "Default")
      (node (ref "CYC_IV_") (pin "U7_29") (pinfunction "B4_U7_29") (pintype "bidirectional"))
      (node (ref "U8") (pin "23") (pinfunction "2B8_23") (pintype "bidirectional"))
    )
    (net (code "77") (name "FPGA_SA1") (class "Default")
      (node (ref "CYC_IV_") (pin "U8_29") (pinfunction "U22_U8_29") (pintype "bidirectional"))
      (node (ref "U8") (pin "22") (pinfunction "2B7_22") (pintype "bidirectional"))
    )
    (net (code "78") (name "FPGA_SA2") (class "Default")
      (node (ref "CYC_IV_") (pin "U7_30") (pinfunction "A4_U7_30") (pintype "bidirectional"))
      (node (ref "U8") (pin "20") (pinfunction "2B6_20") (pintype "bidirectional"))
    )
    (net (code "79") (name "FPGA_SA3") (class "Default")
      (node (ref "CYC_IV_") (pin "U8_30") (pinfunction "U21_U8_30") (pintype "bidirectional"))
      (node (ref "U8") (pin "19") (pinfunction "2B5_19") (pintype "bidirectional"))
    )
    (net (code "80") (name "FPGA_SA4") (class "Default")
      (node (ref "CYC_IV_") (pin "U7_31") (pinfunction "C4_U7_31") (pintype "bidirectional"))
      (node (ref "U8") (pin "17") (pinfunction "2B4_17") (pintype "bidirectional"))
    )
    (net (code "81") (name "FPGA_SA5") (class "Default")
      (node (ref "CYC_IV_") (pin "U8_31") (pinfunction "R22_U8_31") (pintype "bidirectional"))
      (node (ref "U8") (pin "16") (pinfunction "2B3_16") (pintype "bidirectional"))
    )
    (net (code "82") (name "FPGA_SA6") (class "Default")
      (node (ref "CYC_IV_") (pin "U7_32") (pinfunction "C3_U7_32") (pintype "bidirectional"))
      (node (ref "U8") (pin "14") (pinfunction "2B2_14") (pintype "bidirectional"))
    )
    (net (code "83") (name "FPGA_SA7") (class "Default")
      (node (ref "CYC_IV_") (pin "U8_32") (pinfunction "R21_U8_32") (pintype "bidirectional"))
      (node (ref "U8") (pin "13") (pinfunction "2B1_13") (pintype "bidirectional"))
    )
    (net (code "84") (name "FPGA_SA8") (class "Default")
      (node (ref "CYC_IV_") (pin "U7_33") (pinfunction "B5_U7_33") (pintype "bidirectional"))
      (node (ref "U8") (pin "12") (pinfunction "1B8_12") (pintype "bidirectional"))
    )
    (net (code "85") (name "FPGA_SA9") (class "Default")
      (node (ref "CYC_IV_") (pin "U8_33") (pinfunction "P22_U8_33") (pintype "bidirectional"))
      (node (ref "U8") (pin "11") (pinfunction "1B7_11") (pintype "bidirectional"))
    )
    (net (code "86") (name "FPGA_SA10") (class "Default")
      (node (ref "CYC_IV_") (pin "U7_34") (pinfunction "A5_U7_34") (pintype "bidirectional"))
      (node (ref "U8") (pin "9") (pinfunction "1B6_9") (pintype "bidirectional"))
    )
    (net (code "87") (name "FPGA_SA11") (class "Default")
      (node (ref "CYC_IV_") (pin "U8_34") (pinfunction "P21_U8_34") (pintype "bidirectional"))
      (node (ref "U8") (pin "8") (pinfunction "1B5_8") (pintype "bidirectional"))
    )
    (net (code "88") (name "FPGA_SA12") (class "Default")
      (node (ref "CYC_IV_") (pin "U7_35") (pinfunction "B6_U7_35") (pintype "bidirectional"))
      (node (ref "U8") (pin "6") (pinfunction "1B4_6") (pintype "bidirectional"))
    )
    (net (code "89") (name "FPGA_SA13") (class "Default")
      (node (ref "CYC_IV_") (pin "U8_35") (pinfunction "N22_U8_35") (pintype "bidirectional"))
      (node (ref "U8") (pin "5") (pinfunction "1B3_5") (pintype "bidirectional"))
    )
    (net (code "90") (name "FPGA_SA14") (class "Default")
      (node (ref "CYC_IV_") (pin "U7_36") (pinfunction "A6_U7_36") (pintype "bidirectional"))
      (node (ref "U8") (pin "3") (pinfunction "1B2_3") (pintype "bidirectional"))
    )
    (net (code "91") (name "FPGA_SA15") (class "Default")
      (node (ref "CYC_IV_") (pin "U8_36") (pinfunction "N21_U8_36") (pintype "bidirectional"))
      (node (ref "U8") (pin "2") (pinfunction "1B1_2") (pintype "bidirectional"))
    )
    (net (code "92") (name "FPGA_SA16") (class "Default")
      (node (ref "CYC_IV_") (pin "U8_43") (pinfunction "J22_U8_43") (pintype "bidirectional"))
      (node (ref "U10") (pin "19") (pinfunction "2B5_19") (pintype "bidirectional"))
    )
    (net (code "93") (name "FPGA_SA17") (class "Default")
      (node (ref "CYC_IV_") (pin "U7_44") (pinfunction "A10_U7_44") (pintype "bidirectional"))
      (node (ref "U10") (pin "17") (pinfunction "2B4_17") (pintype "bidirectional"))
    )
    (net (code "94") (name "FPGA_SA18") (class "Default")
      (node (ref "CYC_IV_") (pin "U8_44") (pinfunction "J21_U8_44") (pintype "bidirectional"))
      (node (ref "U10") (pin "16") (pinfunction "2B3_16") (pintype "bidirectional"))
    )
    (net (code "95") (name "FPGA_SA19") (class "Default")
      (node (ref "CYC_IV_") (pin "U7_45") (pinfunction "B13_U7_45") (pintype "bidirectional"))
      (node (ref "U10") (pin "14") (pinfunction "2B2_14") (pintype "bidirectional"))
    )
    (net (code "96") (name "FPGA_SA158_DIR") (class "Default")
      (node (ref "CYC_IV_") (pin "U7_41") (pinfunction "B9_U7_41") (pintype "bidirectional"))
      (node (ref "R11") (pin "2") (pinfunction "2_2") (pintype "passive"))
      (node (ref "U8") (pin "1") (pinfunction "1DIR_1") (pintype "input"))
      (node (ref "U8") (pin "24") (pinfunction "2DIR_24") (pintype "input"))
    )
    (net (code "97") (name "FPGA_SBHE") (class "Default")
      (node (ref "CYC_IV_") (pin "U8_14") (pinfunction "AB16_U8_14") (pintype "bidirectional"))
      (node (ref "U12") (pin "2") (pinfunction "1B1_2") (pintype "bidirectional"))
    )
    (net (code "98") (name "FPGA_SD0") (class "Default")
      (node (ref "CYC_IV_") (pin "U7_46") (pinfunction "A13_U7_46") (pintype "bidirectional"))
      (node (ref "U10") (pin "12") (pinfunction "1B8_12") (pintype "bidirectional"))
    )
    (net (code "99") (name "FPGA_SD1") (class "Default")
      (node (ref "CYC_IV_") (pin "U8_46") (pinfunction "H21_U8_46") (pintype "bidirectional"))
      (node (ref "U10") (pin "11") (pinfunction "1B7_11") (pintype "bidirectional"))
    )
    (net (code "100") (name "FPGA_SD2") (class "Default")
      (node (ref "CYC_IV_") (pin "U7_47") (pinfunction "B14_U7_47") (pintype "bidirectional"))
      (node (ref "U10") (pin "9") (pinfunction "1B6_9") (pintype "bidirectional"))
    )
    (net (code "101") (name "FPGA_SD3") (class "Default")
      (node (ref "CYC_IV_") (pin "U8_47") (pinfunction "F22_U8_47") (pintype "bidirectional"))
      (node (ref "U10") (pin "8") (pinfunction "1B5_8") (pintype "bidirectional"))
    )
    (net (code "102") (name "FPGA_SD4") (class "Default")
      (node (ref "CYC_IV_") (pin "U7_48") (pinfunction "A14_U7_48") (pintype "bidirectional"))
      (node (ref "U10") (pin "6") (pinfunction "1B4_6") (pintype "bidirectional"))
    )
    (net (code "103") (name "FPGA_SD5") (class "Default")
      (node (ref "CYC_IV_") (pin "U8_48") (pinfunction "F21_U8_48") (pintype "bidirectional"))
      (node (ref "U10") (pin "5") (pinfunction "1B3_5") (pintype "bidirectional"))
    )
    (net (code "104") (name "FPGA_SD6") (class "Default")
      (node (ref "CYC_IV_") (pin "U7_49") (pinfunction "B15_U7_49") (pintype "bidirectional"))
      (node (ref "U10") (pin "3") (pinfunction "1B2_3") (pintype "bidirectional"))
    )
    (net (code "105") (name "FPGA_SD7") (class "Default")
      (node (ref "CYC_IV_") (pin "U8_49") (pinfunction "E22_U8_49") (pintype "bidirectional"))
      (node (ref "U10") (pin "2") (pinfunction "1B1_2") (pintype "bidirectional"))
    )
    (net (code "106") (name "FPGA_SD8") (class "Default")
      (node (ref "CYC_IV_") (pin "U8_10") (pinfunction "AB14_U8_10") (pintype "bidirectional"))
      (node (ref "U12") (pin "13") (pinfunction "2B1_13") (pintype "bidirectional"))
    )
    (net (code "107") (name "FPGA_SD9") (class "Default")
      (node (ref "CYC_IV_") (pin "U7_10") (pinfunction "P2_U7_10") (pintype "bidirectional"))
      (node (ref "U12") (pin "14") (pinfunction "2B2_14") (pintype "bidirectional"))
    )
    (net (code "108") (name "FPGA_SD10") (class "Default")
      (node (ref "CYC_IV_") (pin "U8_9") (pinfunction "AA14_U8_9") (pintype "bidirectional"))
      (node (ref "U12") (pin "16") (pinfunction "2B3_16") (pintype "bidirectional"))
    )
    (net (code "109") (name "FPGA_SD11") (class "Default")
      (node (ref "CYC_IV_") (pin "U7_9") (pinfunction "P1_U7_9") (pintype "bidirectional"))
      (node (ref "U12") (pin "17") (pinfunction "2B4_17") (pintype "bidirectional"))
    )
    (net (code "110") (name "FPGA_SD12") (class "Default")
      (node (ref "CYC_IV_") (pin "U8_8") (pinfunction "AB13_U8_8") (pintype "bidirectional"))
      (node (ref "U12") (pin "19") (pinfunction "2B5_19") (pintype "bidirectional"))
    )
    (net (code "111") (name "FPGA_SD13") (class "Default")
      (node (ref "CYC_IV_") (pin "U7_8") (pinfunction "R2_U7_8") (pintype "bidirectional"))
      (node (ref "U12") (pin "20") (pinfunction "2B6_20") (pintype "bidirectional"))
    )
    (net (code "112") (name "FPGA_SD14") (class "Default")
      (node (ref "CYC_IV_") (pin "U8_7") (pinfunction "AA13_U8_7") (pintype "bidirectional"))
      (node (ref "U12") (pin "22") (pinfunction "2B7_22") (pintype "bidirectional"))
    )
    (net (code "113") (name "FPGA_SD15") (class "Default")
      (node (ref "CYC_IV_") (pin "U7_7") (pinfunction "R1_U7_7") (pintype "bidirectional"))
      (node (ref "U12") (pin "23") (pinfunction "2B8_23") (pintype "bidirectional"))
    )
    (net (code "114") (name "FPGA_SD70_DIR") (class "Default")
      (node (ref "CYC_IV_") (pin "U8_59") (pinfunction "M20_U8_59") (pintype "bidirectional"))
      (node (ref "R2") (pin "2") (pinfunction "2_2") (pintype "passive"))
      (node (ref "U10") (pin "1") (pinfunction "1DIR_1") (pintype "input"))
    )
    (net (code "115") (name "FPGA_SD158_DIR") (class "Default")
      (node (ref "CYC_IV_") (pin "U8_24") (pinfunction "Y21_U8_24") (pintype "bidirectional"))
      (node (ref "R3") (pin "2") (pinfunction "2_2") (pintype "passive"))
      (node (ref "U12") (pin "24") (pinfunction "2DIR_24") (pintype "input"))
    )
    (net (code "116") (name "FPGA_SMEMR_N") (class "Default")
      (node (ref "CYC_IV_") (pin "U7_42") (pinfunction "A9_U7_42") (pintype "bidirectional"))
      (node (ref "U10") (pin "23") (pinfunction "2B8_23") (pintype "bidirectional"))
    )
    (net (code "117") (name "FPGA_SMEMW_N") (class "Default")
      (node (ref "CYC_IV_") (pin "U8_42") (pinfunction "K21_U8_42") (pintype "bidirectional"))
      (node (ref "U10") (pin "22") (pinfunction "2B7_22") (pintype "bidirectional"))
    )
    (net (code "118") (name "FPGA_TC") (class "Default")
      (node (ref "CYC_IV_") (pin "U7_24") (pinfunction "C2_U7_24") (pintype "bidirectional"))
      (node (ref "U11") (pin "14") (pinfunction "2B2_14") (pintype "bidirectional"))
    )
    (net (code "119") (name "FPGA_ZERO_WAIT") (class "Default")
      (node (ref "CYC_IV_") (pin "U8_40") (pinfunction "L21_U8_40") (pintype "bidirectional"))
      (node (ref "IC2") (pin "2") (pinfunction "I_2") (pintype "input"))
      (node (ref "R4") (pin "2") (pinfunction "2_2") (pintype "passive"))
    )
    (net (code "120") (name "GND") (class "Default")
      (node (ref "C1") (pin "2") (pinfunction "2_2") (pintype "passive"))
      (node (ref "C10") (pin "2") (pinfunction "2_2") (pintype "passive"))
      (node (ref "C11") (pin "2") (pinfunction "2_2") (pintype "passive"))
      (node (ref "C12") (pin "2") (pinfunction "2_2") (pintype "passive"))
      (node (ref "C13") (pin "2") (pinfunction "2_2") (pintype "passive"))
      (node (ref "C14") (pin "2") (pinfunction "2_2") (pintype "passive"))
      (node (ref "C15") (pin "2") (pinfunction "2_2") (pintype "passive"))
      (node (ref "C17") (pin "2") (pinfunction "2_2") (pintype "passive"))
      (node (ref "C18") (pin "2") (pinfunction "2_2") (pintype "passive"))
      (node (ref "C19") (pin "2") (pinfunction "2_2") (pintype "passive"))
      (node (ref "C2") (pin "2") (pinfunction "2_2") (pintype "passive"))
      (node (ref "C20") (pin "2") (pinfunction "2_2") (pintype "passive"))
      (node (ref "C21") (pin "2") (pinfunction "2_2") (pintype "passive"))
      (node (ref "C22") (pin "2") (pinfunction "2_2") (pintype "passive"))
      (node (ref "C26") (pin "1") (pinfunction "1_1") (pintype "passive"))
      (node (ref "C27") (pin "1") (pinfunction "1_1") (pintype "passive"))
      (node (ref "C3") (pin "2") (pinfunction "2_2") (pintype "passive"))
      (node (ref "C4") (pin "2") (pinfunction "2_2") (pintype "passive"))
      (node (ref "C44") (pin "2") (pinfunction "2_2") (pintype "passive"))
      (node (ref "C5") (pin "2") (pinfunction "2_2") (pintype "passive"))
      (node (ref "C58") (pin "2") (pinfunction "2_2") (pintype "passive"))
      (node (ref "C59") (pin "2") (pinfunction "2_2") (pintype "passive"))
      (node (ref "C6") (pin "2") (pinfunction "2_2") (pintype "passive"))
      (node (ref "C60") (pin "1") (pinfunction "1_1") (pintype "passive"))
      (node (ref "C61") (pin "2") (pinfunction "2_2") (pintype "passive"))
      (node (ref "C64") (pin "2") (pinfunction "2_2") (pintype "passive"))
      (node (ref "C65") (pin "1") (pinfunction "1_1") (pintype "passive"))
      (node (ref "C66") (pin "1") (pinfunction "1_1") (pintype "passive"))
      (node (ref "C69") (pin "2") (pinfunction "2_2") (pintype "passive"))
      (node (ref "C7") (pin "2") (pinfunction "2_2") (pintype "passive"))
      (node (ref "C70") (pin "2") (pinfunction "2_2") (pintype "passive"))
      (node (ref "C71") (pin "2") (pinfunction "2_2") (pintype "passive"))
      (node (ref "C72") (pin "1") (pinfunction "1_1") (pintype "passive"))
      (node (ref "C73") (pin "1") (pinfunction "1_1") (pintype "passive"))
      (node (ref "C8") (pin "2") (pinfunction "2_2") (pintype "passive"))
      (node (ref "C9") (pin "2") (pinfunction "2_2") (pintype "passive"))
      (node (ref "CYC_IV_") (pin "JP3_6") (pinfunction "GND_JP3_6") (pintype "power_in"))
      (node (ref "CYC_IV_") (pin "U7_1") (pinfunction "GND_U7_1") (pintype "power_in"))
      (node (ref "CYC_IV_") (pin "U7_2") (pinfunction "GND_U7_2") (pintype "power_in"))
      (node (ref "CYC_IV_") (pin "U7_5") (pinfunction "GND_U7_5") (pintype "power_in"))
      (node (ref "CYC_IV_") (pin "U7_6") (pinfunction "GND_U7_6") (pintype "power_in"))
      (node (ref "CYC_IV_") (pin "U7_61") (pinfunction "GND_U7_61") (pintype "power_in"))
      (node (ref "CYC_IV_") (pin "U7_62") (pinfunction "GND_U7_62") (pintype "power_in"))
      (node (ref "CYC_IV_") (pin "U8_1") (pinfunction "GND_U8_1") (pintype "power_in"))
      (node (ref "CYC_IV_") (pin "U8_2") (pinfunction "GND_U8_2") (pintype "power_in"))
      (node (ref "CYC_IV_") (pin "U8_61") (pinfunction "GND_U8_61") (pintype "power_in"))
      (node (ref "CYC_IV_") (pin "U8_62") (pinfunction "GND_U8_62") (pintype "power_in"))
      (node (ref "IC1") (pin "7") (pinfunction "GND_7") (pintype "power_in"))
      (node (ref "IC10") (pin "7") (pinfunction "VEE_7") (pintype "power_in"))
      (node (ref "IC10") (pin "8") (pinfunction "GND_8") (pintype "power_in"))
      (node (ref "IC11") (pin "7") (pinfunction "VEE_7") (pintype "power_in"))
      (node (ref "IC11") (pin "8") (pinfunction "GND_8") (pintype "power_in"))
      (node (ref "IC2") (pin "3") (pinfunction "GND_3") (pintype "power_in"))
      (node (ref "IC3") (pin "5") (pinfunction "I_5") (pintype "input"))
      (node (ref "IC3") (pin "7") (pinfunction "GND_7") (pintype "power_in"))
      (node (ref "IC4") (pin "1") (pinfunction "OE_1") (pintype "input"))
      (node (ref "IC4") (pin "3") (pinfunction "GND_3") (pintype "power_in"))
      (node (ref "IC6") (pin "12") (pinfunction "AGND_12") (pintype "power_in"))
      (node (ref "IC6") (pin "7") (pinfunction "DGND_7") (pintype "input"))
      (node (ref "IC8") (pin "7") (pinfunction "VEE_7") (pintype "power_in"))
      (node (ref "IC8") (pin "8") (pinfunction "GND_8") (pintype "power_in"))
      (node (ref "IC9") (pin "7") (pinfunction "VEE_7") (pintype "power_in"))
      (node (ref "IC9") (pin "8") (pinfunction "GND_8") (pintype "power_in"))
      (node (ref "ISA") (pin "B1") (pinfunction "GND_B1") (pintype "power_in"))
      (node (ref "ISA") (pin "B10") (pinfunction "GND_B10") (pintype "power_in"))
      (node (ref "ISA") (pin "B31") (pinfunction "GND_B31") (pintype "power_in"))
      (node (ref "ISA") (pin "D18") (pinfunction "GND_D18") (pintype "power_in"))
      (node (ref "R41") (pin "1") (pinfunction "1_1") (pintype "passive"))
      (node (ref "R42") (pin "1") (pinfunction "1_1") (pintype "passive"))
      (node (ref "R63") (pin "2") (pinfunction "2_2") (pintype "passive"))
      (node (ref "R65") (pin "2") (pinfunction "2_2") (pintype "passive"))
      (node (ref "RN3") (pin "1") (pinfunction "1_1") (pintype "passive"))
      (node (ref "RN3") (pin "2") (pinfunction "1_2") (pintype "passive"))
      (node (ref "RN3") (pin "3") (pinfunction "1_3") (pintype "passive"))
      (node (ref "RN3") (pin "4") (pinfunction "1_4") (pintype "passive"))
      (node (ref "U1") (pin "10") (pinfunction "MD0_10") (pintype "bidirectional"))
      (node (ref "U1") (pin "11") (pinfunction "MD1_11") (pintype "bidirectional"))
      (node (ref "U1") (pin "12") (pinfunction "FMT_12") (pintype "bidirectional"))
      (node (ref "U1") (pin "2") (pinfunction "AGND_2") (pintype "bidirectional"))
      (node (ref "U1") (pin "5") (pinfunction "DGND_5") (pintype "bidirectional"))
      (node (ref "U10") (pin "10") (pinfunction "GND_10_10") (pintype "power_in"))
      (node (ref "U10") (pin "15") (pinfunction "GND_15_15") (pintype "power_in"))
      (node (ref "U10") (pin "21") (pinfunction "GND_21_21") (pintype "power_in"))
      (node (ref "U10") (pin "25") (pinfunction "2~{OE}_25") (pintype "input"))
      (node (ref "U10") (pin "28") (pinfunction "GND_28_28") (pintype "power_in"))
      (node (ref "U10") (pin "34") (pinfunction "GND_34_34") (pintype "power_in"))
      (node (ref "U10") (pin "39") (pinfunction "GND_39_39") (pintype "power_in"))
      (node (ref "U10") (pin "4") (pinfunction "GND_4_4") (pintype "power_in"))
      (node (ref "U10") (pin "45") (pinfunction "GND_45_45") (pintype "power_in"))
      (node (ref "U10") (pin "48") (pinfunction "1~{OE}_48") (pintype "input"))
      (node (ref "U11") (pin "10") (pinfunction "GND_10_10") (pintype "power_in"))
      (node (ref "U11") (pin "15") (pinfunction "GND_15_15") (pintype "power_in"))
      (node (ref "U11") (pin "21") (pinfunction "GND_21_21") (pintype "power_in"))
      (node (ref "U11") (pin "25") (pinfunction "2~{OE}_25") (pintype "input"))
      (node (ref "U11") (pin "28") (pinfunction "GND_28_28") (pintype "power_in"))
      (node (ref "U11") (pin "34") (pinfunction "GND_34_34") (pintype "power_in"))
      (node (ref "U11") (pin "39") (pinfunction "GND_39_39") (pintype "power_in"))
      (node (ref "U11") (pin "4") (pinfunction "GND_4_4") (pintype "power_in"))
      (node (ref "U11") (pin "45") (pinfunction "GND_45_45") (pintype "power_in"))
      (node (ref "U11") (pin "48") (pinfunction "1~{OE}_48") (pintype "input"))
      (node (ref "U12") (pin "10") (pinfunction "GND_10_10") (pintype "power_in"))
      (node (ref "U12") (pin "15") (pinfunction "GND_15_15") (pintype "power_in"))
      (node (ref "U12") (pin "21") (pinfunction "GND_21_21") (pintype "power_in"))
      (node (ref "U12") (pin "25") (pinfunction "2~{OE}_25") (pintype "input"))
      (node (ref "U12") (pin "28") (pinfunction "GND_28_28") (pintype "power_in"))
      (node (ref "U12") (pin "34") (pinfunction "GND_34_34") (pintype "power_in"))
      (node (ref "U12") (pin "39") (pinfunction "GND_39_39") (pintype "power_in"))
      (node (ref "U12") (pin "4") (pinfunction "GND_4_4") (pintype "power_in"))
      (node (ref "U12") (pin "45") (pinfunction "GND_45_45") (pintype "power_in"))
      (node (ref "U12") (pin "48") (pinfunction "1~{OE}_48") (pintype "input"))
      (node (ref "U3") (pin "2") (pinfunction "GND_2") (pintype "power_in"))
      (node (ref "U4") (pin "10") (pinfunction "DEMP_10") (pintype "bidirectional"))
      (node (ref "U4") (pin "11") (pinfunction "FLT_11") (pintype "bidirectional"))
      (node (ref "U4") (pin "12") (pinfunction "SCK_12") (pintype "bidirectional"))
      (node (ref "U4") (pin "16") (pinfunction "FMT_16") (pintype "bidirectional"))
      (node (ref "U4") (pin "19") (pinfunction "DGND_19") (pintype "bidirectional"))
      (node (ref "U4") (pin "3") (pinfunction "CPGND_3") (pintype "bidirectional"))
      (node (ref "U4") (pin "9") (pinfunction "AGND_9") (pintype "bidirectional"))
      (node (ref "U7") (pin "2") (pinfunction "GND_2") (pintype "power_in"))
      (node (ref "U8") (pin "10") (pinfunction "GND_10_10") (pintype "power_in"))
      (node (ref "U8") (pin "15") (pinfunction "GND_15_15") (pintype "power_in"))
      (node (ref "U8") (pin "21") (pinfunction "GND_21_21") (pintype "power_in"))
      (node (ref "U8") (pin "25") (pinfunction "2~{OE}_25") (pintype "input"))
      (node (ref "U8") (pin "28") (pinfunction "GND_28_28") (pintype "power_in"))
      (node (ref "U8") (pin "34") (pinfunction "GND_34_34") (pintype "power_in"))
      (node (ref "U8") (pin "39") (pinfunction "GND_39_39") (pintype "power_in"))
      (node (ref "U8") (pin "4") (pinfunction "GND_4_4") (pintype "power_in"))
      (node (ref "U8") (pin "45") (pinfunction "GND_45_45") (pintype "power_in"))
      (node (ref "U8") (pin "48") (pinfunction "1~{OE}_48") (pintype "input"))
      (node (ref "X1") (pin "4") (pinfunction "F_4") (pintype "passive"))
      (node (ref "X1") (pin "5") (pinfunction "F_5") (pintype "passive"))
      (node (ref "X2") (pin "1") (pinfunction "1_1") (pintype "passive"))
      (node (ref "X3") (pin "1") (pinfunction "1_1") (pintype "passive"))
    )
    (net (code "121") (name "I2S_BCK") (class "Default")
      (node (ref "CYC_IV_") (pin "U7_58") (pinfunction "A19_U7_58") (pintype "bidirectional"))
      (node (ref "U1") (pin "8") (pinfunction "BCK_8") (pintype "bidirectional"))
      (node (ref "U4") (pin "13") (pinfunction "BCK_13") (pintype "bidirectional"))
    )
    (net (code "122") (name "I2S_LRCK") (class "Default")
      (node (ref "CYC_IV_") (pin "U7_59") (pinfunction "B20_U7_59") (pintype "bidirectional"))
      (node (ref "U1") (pin "7") (pinfunction "LRCK_7") (pintype "bidirectional"))
      (node (ref "U4") (pin "15") (pinfunction "LRCK_15") (pintype "bidirectional"))
    )
    (net (code "123") (name "I2S_SCK") (class "Default")
      (node (ref "CYC_IV_") (pin "U7_55") (pinfunction "B18_U7_55") (pintype "bidirectional"))
      (node (ref "U1") (pin "6") (pinfunction "SCKI_6") (pintype "bidirectional"))
    )
    (net (code "124") (name "IRQ3") (class "Default")
      (node (ref "ISA") (pin "B25") (pinfunction "IRQ3_B25") (pintype "input"))
    )
    (net (code "125") (name "IRQ4") (class "Default")
      (node (ref "ISA") (pin "B24") (pinfunction "IRQ4_B24") (pintype "input"))
    )
    (net (code "126") (name "IRQ5") (class "Default")
      (node (ref "IC8") (pin "13") (pinfunction "X0_13") (pintype "bidirectional"))
      (node (ref "IC9") (pin "13") (pinfunction "X0_13") (pintype "bidirectional"))
      (node (ref "ISA") (pin "B23") (pinfunction "IRQ5_B23") (pintype "input"))
    )
    (net (code "127") (name "IRQ6") (class "Default")
      (node (ref "IC8") (pin "14") (pinfunction "X1_14") (pintype "bidirectional"))
      (node (ref "IC9") (pin "14") (pinfunction "X1_14") (pintype "bidirectional"))
      (node (ref "ISA") (pin "B22") (pinfunction "IRQ6_B22") (pintype "input"))
    )
    (net (code "128") (name "IRQ7") (class "Default")
      (node (ref "IC8") (pin "15") (pinfunction "X2_15") (pintype "bidirectional"))
      (node (ref "IC9") (pin "15") (pinfunction "X2_15") (pintype "bidirectional"))
      (node (ref "ISA") (pin "B21") (pinfunction "IRQ7_B21") (pintype "input"))
    )
    (net (code "129") (name "IRQ9") (class "Default")
      (node (ref "ISA") (pin "B4") (pinfunction "IRQ9_B4") (pintype "input"))
    )
    (net (code "130") (name "IRQ10") (class "Default")
      (node (ref "IC8") (pin "12") (pinfunction "X3_12") (pintype "bidirectional"))
      (node (ref "IC9") (pin "12") (pinfunction "X3_12") (pintype "bidirectional"))
      (node (ref "ISA") (pin "D3") (pinfunction "IRQ10_D3") (pintype "input"))
    )
    (net (code "131") (name "IRQ11") (class "Default")
      (node (ref "IC8") (pin "1") (pinfunction "X4_1") (pintype "bidirectional"))
      (node (ref "IC9") (pin "1") (pinfunction "X4_1") (pintype "bidirectional"))
      (node (ref "ISA") (pin "D4") (pinfunction "IRQ11_D4") (pintype "input"))
    )
    (net (code "132") (name "IRQ12") (class "Default")
      (node (ref "IC8") (pin "5") (pinfunction "X5_5") (pintype "bidirectional"))
      (node (ref "IC9") (pin "5") (pinfunction "X5_5") (pintype "bidirectional"))
      (node (ref "ISA") (pin "D5") (pinfunction "IRQ12_D5") (pintype "input"))
    )
    (net (code "133") (name "IRQ14") (class "Default")
      (node (ref "IC8") (pin "2") (pinfunction "X6_2") (pintype "bidirectional"))
      (node (ref "IC9") (pin "2") (pinfunction "X6_2") (pintype "bidirectional"))
      (node (ref "ISA") (pin "D7") (pinfunction "IRQ14_D7") (pintype "input"))
    )
    (net (code "134") (name "IRQ15") (class "Default")
      (node (ref "IC8") (pin "4") (pinfunction "X7_4") (pintype "bidirectional"))
      (node (ref "IC9") (pin "4") (pinfunction "X7_4") (pintype "bidirectional"))
      (node (ref "ISA") (pin "D6") (pinfunction "IRQ15_D6") (pintype "input"))
    )
    (net (code "135") (name "IRQ_HI_SEL_A0") (class "Default")
      (node (ref "CYC_IV_") (pin "U8_38") (pinfunction "M21_U8_38") (pintype "bidirectional"))
      (node (ref "IC9") (pin "11") (pinfunction "A_11") (pintype "input"))
    )
    (net (code "136") (name "IRQ_HI_SEL_A1") (class "Default")
      (node (ref "CYC_IV_") (pin "U8_39") (pinfunction "L22_U8_39") (pintype "bidirectional"))
      (node (ref "IC9") (pin "10") (pinfunction "B_10") (pintype "input"))
    )
    (net (code "137") (name "IRQ_HI_SEL_A2") (class "Default")
      (node (ref "CYC_IV_") (pin "U8_41") (pinfunction "K22_U8_41") (pintype "bidirectional"))
      (node (ref "IC9") (pin "9") (pinfunction "C_9") (pintype "input"))
    )
    (net (code "138") (name "IRQ_HI_TRIG_N") (class "Default")
      (node (ref "CYC_IV_") (pin "U8_37") (pinfunction "M22_U8_37") (pintype "bidirectional"))
      (node (ref "IC9") (pin "6") (pinfunction "INH_6") (pintype "input"))
      (node (ref "R8") (pin "1") (pinfunction "1_1") (pintype "passive"))
    )
    (net (code "139") (name "IRQ_LO_SEL_A0") (class "Default")
      (node (ref "CYC_IV_") (pin "U7_37") (pinfunction "B7_U7_37") (pintype "bidirectional"))
      (node (ref "IC8") (pin "11") (pinfunction "A_11") (pintype "input"))
    )
    (net (code "140") (name "IRQ_LO_SEL_A1") (class "Default")
      (node (ref "CYC_IV_") (pin "U7_40") (pinfunction "A8_U7_40") (pintype "bidirectional"))
      (node (ref "IC8") (pin "10") (pinfunction "B_10") (pintype "input"))
    )
    (net (code "141") (name "IRQ_LO_SEL_A2") (class "Default")
      (node (ref "CYC_IV_") (pin "U7_39") (pinfunction "B8_U7_39") (pintype "bidirectional"))
      (node (ref "IC8") (pin "9") (pinfunction "C_9") (pintype "input"))
    )
    (net (code "142") (name "IRQ_LO_TRIG_N") (class "Default")
      (node (ref "CYC_IV_") (pin "U7_38") (pinfunction "A7_U7_38") (pintype "bidirectional"))
      (node (ref "IC8") (pin "6") (pinfunction "INH_6") (pintype "input"))
      (node (ref "R7") (pin "1") (pinfunction "1_1") (pintype "passive"))
    )
    (net (code "143") (name "I{slash}OCHRDY") (class "Default")
      (node (ref "IC1") (pin "4") (pinfunction "O_4") (pintype "open_collector"))
      (node (ref "ISA") (pin "A10") (pinfunction "I/OCHRDY_A10") (pintype "input"))
    )
    (net (code "144") (name "I{slash}O_CHCK") (class "Default")
      (node (ref "IC1") (pin "2") (pinfunction "O_2") (pintype "open_collector"))
      (node (ref "ISA") (pin "A1") (pinfunction "I/O_CHCK_A1") (pintype "input"))
    )
    (net (code "145") (name "I{slash}~{OCS16}") (class "Default")
      (node (ref "IC1") (pin "6") (pinfunction "O_6") (pintype "open_collector"))
      (node (ref "ISA") (pin "D2") (pinfunction "I/~{OCS16}_D2") (pintype "input"))
    )
    (net (code "146") (name "JOY_B1_N") (class "Default")
      (node (ref "IC3") (pin "13") (pinfunction "I_13") (pintype "input"))
      (node (ref "RN4") (pin "1") (pinfunction "1_1") (pintype "passive"))
      (node (ref "X1") (pin "2") (pinfunction "F_2") (pintype "passive"))
    )
    (net (code "147") (name "JOY_B2_N") (class "Default")
      (node (ref "IC3") (pin "11") (pinfunction "I_11") (pintype "input"))
      (node (ref "RN4") (pin "2") (pinfunction "1_2") (pintype "passive"))
      (node (ref "X1") (pin "7") (pinfunction "F_7") (pintype "passive"))
    )
    (net (code "148") (name "JOY_B3_N") (class "Default")
      (node (ref "IC3") (pin "9") (pinfunction "I_9") (pintype "input"))
      (node (ref "RN4") (pin "3") (pinfunction "1_3") (pintype "passive"))
      (node (ref "X1") (pin "10") (pinfunction "F_10") (pintype "passive"))
    )
    (net (code "149") (name "JOY_B4_N") (class "Default")
      (node (ref "IC3") (pin "1") (pinfunction "I_1") (pintype "input"))
      (node (ref "RN4") (pin "4") (pinfunction "1_4") (pintype "passive"))
      (node (ref "X1") (pin "14") (pinfunction "F_14") (pintype "passive"))
    )
    (net (code "150") (name "JOY_CLK") (class "Default")
      (node (ref "CYC_IV_") (pin "U8_57") (pinfunction "N20_U8_57") (pintype "bidirectional"))
      (node (ref "IC6") (pin "11") (pinfunction "CLK_11") (pintype "input"))
    )
    (net (code "151") (name "JOY_CS_N") (class "Default")
      (node (ref "CYC_IV_") (pin "U8_51") (pinfunction "D22_U8_51") (pintype "bidirectional"))
      (node (ref "IC6") (pin "8") (pinfunction "/CS_8") (pintype "input"))
    )
    (net (code "152") (name "JOY_DIN") (class "Default")
      (node (ref "CYC_IV_") (pin "U8_53") (pinfunction "C22_U8_53") (pintype "bidirectional"))
      (node (ref "IC6") (pin "9") (pinfunction "DIN_9") (pintype "input"))
    )
    (net (code "153") (name "JOY_DOUT") (class "Default")
      (node (ref "CYC_IV_") (pin "U8_55") (pinfunction "B22_U8_55") (pintype "bidirectional"))
      (node (ref "IC6") (pin "10") (pinfunction "DOUT_10") (pintype "output"))
    )
    (net (code "154") (name "JOY_X1") (class "Default")
      (node (ref "RN2") (pin "1") (pinfunction "1_1") (pintype "passive"))
      (node (ref "X1") (pin "3") (pinfunction "F_3") (pintype "passive"))
    )
    (net (code "155") (name "JOY_X2") (class "Default")
      (node (ref "RN2") (pin "2") (pinfunction "1_2") (pintype "passive"))
      (node (ref "X1") (pin "11") (pinfunction "F_11") (pintype "passive"))
    )
    (net (code "156") (name "JOY_Y1") (class "Default")
      (node (ref "RN2") (pin "4") (pinfunction "1_4") (pintype "passive"))
      (node (ref "X1") (pin "6") (pinfunction "F_6") (pintype "passive"))
    )
    (net (code "157") (name "JOY_Y2") (class "Default")
      (node (ref "RN2") (pin "3") (pinfunction "1_3") (pintype "passive"))
      (node (ref "X1") (pin "13") (pinfunction "F_13") (pintype "passive"))
    )
    (net (code "158") (name "LA17") (class "Default")
      (node (ref "ISA") (pin "C8") (pinfunction "LA17_C8") (pintype "bidirectional"))
      (node (ref "U12") (pin "37") (pinfunction "1A8_37") (pintype "bidirectional"))
    )
    (net (code "159") (name "LA18") (class "Default")
      (node (ref "ISA") (pin "C7") (pinfunction "LA18_C7") (pintype "bidirectional"))
      (node (ref "U12") (pin "38") (pinfunction "1A7_38") (pintype "bidirectional"))
    )
    (net (code "160") (name "LA19") (class "Default")
      (node (ref "ISA") (pin "C6") (pinfunction "LA19_C6") (pintype "bidirectional"))
      (node (ref "U12") (pin "40") (pinfunction "1A6_40") (pintype "bidirectional"))
    )
    (net (code "161") (name "LA20") (class "Default")
      (node (ref "ISA") (pin "C5") (pinfunction "LA20_C5") (pintype "bidirectional"))
      (node (ref "U12") (pin "41") (pinfunction "1A5_41") (pintype "bidirectional"))
    )
    (net (code "162") (name "LA21") (class "Default")
      (node (ref "ISA") (pin "C4") (pinfunction "LA21_C4") (pintype "bidirectional"))
      (node (ref "U12") (pin "43") (pinfunction "1A4_43") (pintype "bidirectional"))
    )
    (net (code "163") (name "LA22") (class "Default")
      (node (ref "ISA") (pin "C3") (pinfunction "LA22_C3") (pintype "bidirectional"))
      (node (ref "U12") (pin "44") (pinfunction "1A3_44") (pintype "bidirectional"))
    )
    (net (code "164") (name "LA23") (class "Default")
      (node (ref "ISA") (pin "C2") (pinfunction "LA23_C2") (pintype "bidirectional"))
      (node (ref "U12") (pin "46") (pinfunction "1A2_46") (pintype "bidirectional"))
    )
    (net (code "165") (name "MIDI_RXD") (class "Default")
      (node (ref "IC3") (pin "3") (pinfunction "I_3") (pintype "input"))
      (node (ref "X1") (pin "12") (pinfunction "F_12") (pintype "passive"))
    )
    (net (code "166") (name "MIDI_TXD") (class "Default")
      (node (ref "IC4") (pin "4") (pinfunction "O_4") (pintype "tri_state"))
      (node (ref "X1") (pin "15") (pinfunction "F_15") (pintype "passive"))
    )
    (net (code "167") (name "N$8") (class "Default")
      (node (ref "CYC_IV_") (pin "U7_20") (pinfunction "F2_U7_20") (pintype "bidirectional"))
    )
    (net (code "168") (name "N$9") (class "Default")
      (node (ref "CYC_IV_") (pin "U7_28") (pinfunction "A3_U7_28") (pintype "bidirectional"))
    )
    (net (code "169") (name "NCONFIG") (class "Default")
      (node (ref "CYC_IV_") (pin "JP3_3") (pinfunction "NCONFIG_JP3_3") (pintype "input"))
    )
    (net (code "170") (name "NSTATUS") (class "Default")
      (node (ref "CYC_IV_") (pin "JP3_4") (pinfunction "NSTATUS_JP3_4") (pintype "input"))
    )
    (net (code "171") (name "Net-(C24-Pad-)") (class "Default")
      (node (ref "C24") (pin "-") (pinfunction "-_-") (pintype "passive"))
      (node (ref "X3") (pin "3") (pinfunction "3_3") (pintype "passive"))
    )
    (net (code "172") (name "Net-(C25-Pad-)") (class "Default")
      (node (ref "C25") (pin "-") (pinfunction "-_-") (pintype "passive"))
      (node (ref "X3") (pin "2") (pinfunction "2_2") (pintype "passive"))
    )
    (net (code "173") (name "Net-(C67-Pad-)") (class "Default")
      (node (ref "C67") (pin "-") (pinfunction "-_-") (pintype "passive"))
      (node (ref "X2") (pin "2") (pinfunction "2_2") (pintype "passive"))
    )
    (net (code "174") (name "Net-(C68-Pad-)") (class "Default")
      (node (ref "C68") (pin "-") (pinfunction "-_-") (pintype "passive"))
      (node (ref "X2") (pin "3") (pinfunction "3_3") (pintype "passive"))
    )
    (net (code "175") (name "Net-(IC6-CH0)") (class "Default")
      (node (ref "IC6") (pin "1") (pinfunction "CH0_1") (pintype "input"))
      (node (ref "RN2") (pin "8") (pinfunction "2_8") (pintype "passive"))
      (node (ref "RN3") (pin "5") (pinfunction "2_5") (pintype "passive"))
    )
    (net (code "176") (name "Net-(IC6-CH1)") (class "Default")
      (node (ref "IC6") (pin "2") (pinfunction "CH1_2") (pintype "input"))
      (node (ref "RN2") (pin "7") (pinfunction "2_7") (pintype "passive"))
      (node (ref "RN3") (pin "6") (pinfunction "2_6") (pintype "passive"))
    )
    (net (code "177") (name "Net-(IC6-CH2)") (class "Default")
      (node (ref "IC6") (pin "3") (pinfunction "CH2_3") (pintype "input"))
      (node (ref "RN2") (pin "6") (pinfunction "2_6") (pintype "passive"))
      (node (ref "RN3") (pin "7") (pinfunction "2_7") (pintype "passive"))
    )
    (net (code "178") (name "Net-(IC6-CH3)") (class "Default")
      (node (ref "IC6") (pin "4") (pinfunction "CH3_4") (pintype "input"))
      (node (ref "RN2") (pin "5") (pinfunction "2_5") (pintype "passive"))
      (node (ref "RN3") (pin "8") (pinfunction "2_8") (pintype "passive"))
    )
    (net (code "179") (name "Net-(U1-VINL)") (class "Default")
      (node (ref "C26") (pin "2") (pinfunction "2_2") (pintype "passive"))
      (node (ref "R39") (pin "2") (pinfunction "2_2") (pintype "passive"))
      (node (ref "R42") (pin "2") (pinfunction "2_2") (pintype "passive"))
      (node (ref "U1") (pin "13") (pinfunction "VINL_13") (pintype "bidirectional"))
    )
    (net (code "180") (name "Net-(U1-VINR)") (class "Default")
      (node (ref "C27") (pin "2") (pinfunction "2_2") (pintype "passive"))
      (node (ref "R40") (pin "2") (pinfunction "2_2") (pintype "passive"))
      (node (ref "R41") (pin "2") (pinfunction "2_2") (pintype "passive"))
      (node (ref "U1") (pin "14") (pinfunction "VINR_14") (pintype "bidirectional"))
    )
    (net (code "181") (name "Net-(U1-VREF)") (class "Default")
      (node (ref "C64") (pin "1") (pinfunction "1_1") (pintype "passive"))
      (node (ref "U1") (pin "1") (pinfunction "VREF_1") (pintype "bidirectional"))
    )
    (net (code "182") (name "Net-(U4-CAPM)") (class "Default")
      (node (ref "C41") (pin "2") (pinfunction "2_2") (pintype "passive"))
      (node (ref "U4") (pin "4") (pinfunction "CAPM_4") (pintype "bidirectional"))
    )
    (net (code "183") (name "Net-(U4-CAPP)") (class "Default")
      (node (ref "C41") (pin "1") (pinfunction "1_1") (pintype "passive"))
      (node (ref "U4") (pin "2") (pinfunction "CAPP_2") (pintype "bidirectional"))
    )
    (net (code "184") (name "Net-(U4-LDOO)") (class "Default")
      (node (ref "C59") (pin "1") (pinfunction "1_1") (pintype "passive"))
      (node (ref "C61") (pin "1") (pinfunction "1_1") (pintype "passive"))
      (node (ref "U4") (pin "18") (pinfunction "LDOO_18") (pintype "bidirectional"))
    )
    (net (code "185") (name "Net-(U4-OUTL)") (class "Default")
      (node (ref "R112") (pin "2") (pinfunction "2_2") (pintype "passive"))
      (node (ref "U4") (pin "6") (pinfunction "OUTL_6") (pintype "bidirectional"))
    )
    (net (code "186") (name "Net-(U4-OUTR)") (class "Default")
      (node (ref "R113") (pin "2") (pinfunction "2_2") (pintype "passive"))
      (node (ref "U4") (pin "7") (pinfunction "OUTR_7") (pintype "bidirectional"))
    )
    (net (code "187") (name "Net-(U4-VNEG)") (class "Default")
      (node (ref "C60") (pin "2") (pinfunction "2_2") (pintype "passive"))
      (node (ref "U4") (pin "5") (pinfunction "VNEG_5") (pintype "bidirectional"))
    )
    (net (code "188") (name "OSC") (class "Default")
      (node (ref "ISA") (pin "B30") (pinfunction "OSC_B30") (pintype "output"))
      (node (ref "U11") (pin "32") (pinfunction "2A4_32") (pintype "bidirectional"))
    )
    (net (code "189") (name "RES_DRV") (class "Default")
      (node (ref "ISA") (pin "B2") (pinfunction "RES_DRV_B2") (pintype "output"))
      (node (ref "U10") (pin "29") (pinfunction "2A6_29") (pintype "bidirectional"))
    )
    (net (code "190") (name "SA0") (class "Default")
      (node (ref "ISA") (pin "A31") (pinfunction "SA0_A31") (pintype "bidirectional"))
      (node (ref "U8") (pin "26") (pinfunction "2A8_26") (pintype "bidirectional"))
    )
    (net (code "191") (name "SA1") (class "Default")
      (node (ref "ISA") (pin "A30") (pinfunction "SA1_A30") (pintype "bidirectional"))
      (node (ref "U8") (pin "27") (pinfunction "2A7_27") (pintype "bidirectional"))
    )
    (net (code "192") (name "SA2") (class "Default")
      (node (ref "ISA") (pin "A29") (pinfunction "SA2_A29") (pintype "bidirectional"))
      (node (ref "U8") (pin "29") (pinfunction "2A6_29") (pintype "bidirectional"))
    )
    (net (code "193") (name "SA3") (class "Default")
      (node (ref "ISA") (pin "A28") (pinfunction "SA3_A28") (pintype "bidirectional"))
      (node (ref "U8") (pin "30") (pinfunction "2A5_30") (pintype "bidirectional"))
    )
    (net (code "194") (name "SA4") (class "Default")
      (node (ref "ISA") (pin "A27") (pinfunction "SA4_A27") (pintype "bidirectional"))
      (node (ref "U8") (pin "32") (pinfunction "2A4_32") (pintype "bidirectional"))
    )
    (net (code "195") (name "SA5") (class "Default")
      (node (ref "ISA") (pin "A26") (pinfunction "SA5_A26") (pintype "bidirectional"))
      (node (ref "U8") (pin "33") (pinfunction "2A3_33") (pintype "bidirectional"))
    )
    (net (code "196") (name "SA6") (class "Default")
      (node (ref "ISA") (pin "A25") (pinfunction "SA6_A25") (pintype "bidirectional"))
      (node (ref "U8") (pin "35") (pinfunction "2A2_35") (pintype "bidirectional"))
    )
    (net (code "197") (name "SA7") (class "Default")
      (node (ref "ISA") (pin "A24") (pinfunction "SA7_A24") (pintype "bidirectional"))
      (node (ref "U8") (pin "36") (pinfunction "2A1_36") (pintype "bidirectional"))
    )
    (net (code "198") (name "SA8") (class "Default")
      (node (ref "ISA") (pin "A23") (pinfunction "SA8_A23") (pintype "bidirectional"))
      (node (ref "U8") (pin "37") (pinfunction "1A8_37") (pintype "bidirectional"))
    )
    (net (code "199") (name "SA9") (class "Default")
      (node (ref "ISA") (pin "A22") (pinfunction "SA9_A22") (pintype "bidirectional"))
      (node (ref "U8") (pin "38") (pinfunction "1A7_38") (pintype "bidirectional"))
    )
    (net (code "200") (name "SA10") (class "Default")
      (node (ref "ISA") (pin "A21") (pinfunction "SA10_A21") (pintype "bidirectional"))
      (node (ref "U8") (pin "40") (pinfunction "1A6_40") (pintype "bidirectional"))
    )
    (net (code "201") (name "SA11") (class "Default")
      (node (ref "ISA") (pin "A20") (pinfunction "SA11_A20") (pintype "bidirectional"))
      (node (ref "U8") (pin "41") (pinfunction "1A5_41") (pintype "bidirectional"))
    )
    (net (code "202") (name "SA12") (class "Default")
      (node (ref "ISA") (pin "A19") (pinfunction "SA12_A19") (pintype "bidirectional"))
      (node (ref "U8") (pin "43") (pinfunction "1A4_43") (pintype "bidirectional"))
    )
    (net (code "203") (name "SA13") (class "Default")
      (node (ref "ISA") (pin "A18") (pinfunction "SA13_A18") (pintype "bidirectional"))
      (node (ref "U8") (pin "44") (pinfunction "1A3_44") (pintype "bidirectional"))
    )
    (net (code "204") (name "SA14") (class "Default")
      (node (ref "ISA") (pin "A17") (pinfunction "SA14_A17") (pintype "bidirectional"))
      (node (ref "U8") (pin "46") (pinfunction "1A2_46") (pintype "bidirectional"))
    )
    (net (code "205") (name "SA15") (class "Default")
      (node (ref "ISA") (pin "A16") (pinfunction "SA15_A16") (pintype "bidirectional"))
      (node (ref "U8") (pin "47") (pinfunction "1A1_47") (pintype "bidirectional"))
    )
    (net (code "206") (name "SA16") (class "Default")
      (node (ref "ISA") (pin "A15") (pinfunction "SA16_A15") (pintype "bidirectional"))
      (node (ref "U10") (pin "30") (pinfunction "2A5_30") (pintype "bidirectional"))
    )
    (net (code "207") (name "SA17") (class "Default")
      (node (ref "ISA") (pin "A14") (pinfunction "SA17_A14") (pintype "bidirectional"))
      (node (ref "U10") (pin "32") (pinfunction "2A4_32") (pintype "bidirectional"))
    )
    (net (code "208") (name "SA18") (class "Default")
      (node (ref "ISA") (pin "A13") (pinfunction "SA18_A13") (pintype "bidirectional"))
      (node (ref "U10") (pin "33") (pinfunction "2A3_33") (pintype "bidirectional"))
    )
    (net (code "209") (name "SA19") (class "Default")
      (node (ref "ISA") (pin "A12") (pinfunction "SA19_A12") (pintype "bidirectional"))
      (node (ref "U10") (pin "35") (pinfunction "2A2_35") (pintype "bidirectional"))
    )
    (net (code "210") (name "SBHE") (class "Default")
      (node (ref "ISA") (pin "C1") (pinfunction "SBHE_C1") (pintype "bidirectional"))
      (node (ref "U12") (pin "47") (pinfunction "1A1_47") (pintype "bidirectional"))
    )
    (net (code "211") (name "SD0") (class "Default")
      (node (ref "ISA") (pin "A9") (pinfunction "SD0_A9") (pintype "bidirectional"))
      (node (ref "U10") (pin "37") (pinfunction "1A8_37") (pintype "bidirectional"))
    )
    (net (code "212") (name "SD1") (class "Default")
      (node (ref "ISA") (pin "A8") (pinfunction "SD1_A8") (pintype "bidirectional"))
      (node (ref "U10") (pin "38") (pinfunction "1A7_38") (pintype "bidirectional"))
    )
    (net (code "213") (name "SD2") (class "Default")
      (node (ref "ISA") (pin "A7") (pinfunction "SD2_A7") (pintype "bidirectional"))
      (node (ref "U10") (pin "40") (pinfunction "1A6_40") (pintype "bidirectional"))
    )
    (net (code "214") (name "SD3") (class "Default")
      (node (ref "ISA") (pin "A6") (pinfunction "SD3_A6") (pintype "bidirectional"))
      (node (ref "U10") (pin "41") (pinfunction "1A5_41") (pintype "bidirectional"))
    )
    (net (code "215") (name "SD4") (class "Default")
      (node (ref "ISA") (pin "A5") (pinfunction "SD4_A5") (pintype "bidirectional"))
      (node (ref "U10") (pin "43") (pinfunction "1A4_43") (pintype "bidirectional"))
    )
    (net (code "216") (name "SD5") (class "Default")
      (node (ref "ISA") (pin "A4") (pinfunction "SD5_A4") (pintype "bidirectional"))
      (node (ref "U10") (pin "44") (pinfunction "1A3_44") (pintype "bidirectional"))
    )
    (net (code "217") (name "SD6") (class "Default")
      (node (ref "ISA") (pin "A3") (pinfunction "SD6_A3") (pintype "bidirectional"))
      (node (ref "U10") (pin "46") (pinfunction "1A2_46") (pintype "bidirectional"))
    )
    (net (code "218") (name "SD7") (class "Default")
      (node (ref "ISA") (pin "A2") (pinfunction "SD7_A2") (pintype "bidirectional"))
      (node (ref "U10") (pin "47") (pinfunction "1A1_47") (pintype "bidirectional"))
    )
    (net (code "219") (name "SD8") (class "Default")
      (node (ref "ISA") (pin "C11") (pinfunction "SD8_C11") (pintype "bidirectional"))
      (node (ref "U12") (pin "36") (pinfunction "2A1_36") (pintype "bidirectional"))
    )
    (net (code "220") (name "SD9") (class "Default")
      (node (ref "ISA") (pin "C12") (pinfunction "SD9_C12") (pintype "bidirectional"))
      (node (ref "U12") (pin "35") (pinfunction "2A2_35") (pintype "bidirectional"))
    )
    (net (code "221") (name "SD10") (class "Default")
      (node (ref "ISA") (pin "C13") (pinfunction "SD10_C13") (pintype "bidirectional"))
      (node (ref "U12") (pin "33") (pinfunction "2A3_33") (pintype "bidirectional"))
    )
    (net (code "222") (name "SD11") (class "Default")
      (node (ref "ISA") (pin "C14") (pinfunction "SD11_C14") (pintype "bidirectional"))
      (node (ref "U12") (pin "32") (pinfunction "2A4_32") (pintype "bidirectional"))
    )
    (net (code "223") (name "SD12") (class "Default")
      (node (ref "ISA") (pin "C15") (pinfunction "SD12_C15") (pintype "bidirectional"))
      (node (ref "U12") (pin "30") (pinfunction "2A5_30") (pintype "bidirectional"))
    )
    (net (code "224") (name "SD13") (class "Default")
      (node (ref "ISA") (pin "C16") (pinfunction "SD13_C16") (pintype "bidirectional"))
      (node (ref "U12") (pin "29") (pinfunction "2A6_29") (pintype "bidirectional"))
    )
    (net (code "225") (name "SD14") (class "Default")
      (node (ref "ISA") (pin "C17") (pinfunction "SD14_C17") (pintype "bidirectional"))
      (node (ref "U12") (pin "27") (pinfunction "2A7_27") (pintype "bidirectional"))
    )
    (net (code "226") (name "SD15") (class "Default")
      (node (ref "ISA") (pin "C18") (pinfunction "SD15_C18") (pintype "bidirectional"))
      (node (ref "U12") (pin "26") (pinfunction "2A8_26") (pintype "bidirectional"))
    )
    (net (code "227") (name "T{slash}C") (class "Default")
      (node (ref "ISA") (pin "B27") (pinfunction "T/C_B27") (pintype "output"))
      (node (ref "U11") (pin "35") (pinfunction "2A2_35") (pintype "bidirectional"))
    )
    (net (code "228") (name "unconnected-(CYC_IV_B-B1-PadU7_25)") (class "Default")
      (node (ref "CYC_IV_") (pin "U7_25") (pinfunction "B1_U7_25") (pintype "bidirectional"))
    )
    (net (code "229") (name "unconnected-(CYC_IV_B-C1-PadU7_23)") (class "Default")
      (node (ref "CYC_IV_") (pin "U7_23") (pinfunction "C1_U7_23") (pintype "bidirectional"))
    )
    (net (code "230") (name "unconnected-(CYC_IV_B-F1-PadU7_19)") (class "Default")
      (node (ref "CYC_IV_") (pin "U7_19") (pinfunction "F1_U7_19") (pintype "bidirectional"))
    )
    (net (code "231") (name "unconnected-(IC3F-O-Pad6)") (class "Default")
      (node (ref "IC3") (pin "6") (pinfunction "O_6") (pintype "output"))
    )
    (net (code "232") (name "unconnected-(IC6-NC-Pad5)") (class "Default")
      (node (ref "IC6") (pin "5") (pinfunction "NC_5") (pintype "input"))
    )
    (net (code "233") (name "unconnected-(IC6-NC-Pad6)") (class "Default")
      (node (ref "IC6") (pin "6") (pinfunction "NC_6") (pintype "input"))
    )
    (net (code "234") (name "unconnected-(IC10A-X4-Pad1)") (class "Default")
      (node (ref "IC10") (pin "1") (pinfunction "X4_1") (pintype "bidirectional"))
    )
    (net (code "235") (name "unconnected-(IC11A-X4-Pad1)") (class "Default")
      (node (ref "IC11") (pin "1") (pinfunction "X4_1") (pintype "bidirectional"))
    )
    (net (code "236") (name "unconnected-(ISAB-+12VDC-PadB9)") (class "Default")
      (node (ref "ISA") (pin "B9") (pinfunction "+12VDC_B9") (pintype "power_in"))
    )
    (net (code "237") (name "unconnected-(ISAB--12VDC-PadB7)") (class "Default")
      (node (ref "ISA") (pin "B7") (pinfunction "-12VDC_B7") (pintype "power_in"))
    )
    (net (code "238") (name "unconnected-(U3-ADJ-Pad4)") (class "Default")
      (node (ref "U3") (pin "4") (pinfunction "ADJ_4") (pintype "passive"))
    )
    (net (code "239") (name "unconnected-(U7-ADJ-Pad4)") (class "Default")
      (node (ref "U7") (pin "4") (pinfunction "ADJ_4") (pintype "passive"))
    )
    (net (code "240") (name "unconnected-(U11-1A7-Pad38)") (class "Default")
      (node (ref "U11") (pin "38") (pinfunction "1A7_38") (pintype "bidirectional"))
    )
    (net (code "241") (name "unconnected-(U11-1B7-Pad11)") (class "Default")
      (node (ref "U11") (pin "11") (pinfunction "1B7_11") (pintype "bidirectional"))
    )
    (net (code "242") (name "unconnected-(X2-Pad4)") (class "Default")
      (node (ref "X2") (pin "4") (pinfunction "4_4") (pintype "passive"))
    )
    (net (code "243") (name "unconnected-(X2-Pad5)") (class "Default")
      (node (ref "X2") (pin "5") (pinfunction "5_5") (pintype "passive"))
    )
    (net (code "244") (name "unconnected-(X3-Pad4)") (class "Default")
      (node (ref "X3") (pin "4") (pinfunction "4_4") (pintype "passive"))
    )
    (net (code "245") (name "unconnected-(X3-Pad5)") (class "Default")
      (node (ref "X3") (pin "5") (pinfunction "5_5") (pintype "passive"))
    )
    (net (code "246") (name "~{DACK0}") (class "Default")
      (node (ref "ISA") (pin "D8") (pinfunction "~{DACK0}_D8") (pintype "output"))
      (node (ref "U11") (pin "30") (pinfunction "2A5_30") (pintype "bidirectional"))
    )
    (net (code "247") (name "~{DACK1}") (class "Default")
      (node (ref "ISA") (pin "B17") (pinfunction "~{DACK1}_B17") (pintype "output"))
      (node (ref "U11") (pin "40") (pinfunction "1A6_40") (pintype "bidirectional"))
    )
    (net (code "248") (name "~{DACK2}") (class "Default")
      (node (ref "ISA") (pin "B26") (pinfunction "~{DACK2}_B26") (pintype "output"))
      (node (ref "U11") (pin "36") (pinfunction "2A1_36") (pintype "bidirectional"))
    )
    (net (code "249") (name "~{DACK3}") (class "Default")
      (node (ref "ISA") (pin "B15") (pinfunction "~{DACK3}_B15") (pintype "output"))
      (node (ref "U11") (pin "41") (pinfunction "1A5_41") (pintype "bidirectional"))
    )
    (net (code "250") (name "~{DACK5}") (class "Default")
      (node (ref "ISA") (pin "D10") (pinfunction "~{DACK5}_D10") (pintype "output"))
      (node (ref "U11") (pin "29") (pinfunction "2A6_29") (pintype "bidirectional"))
    )
    (net (code "251") (name "~{DACK6}") (class "Default")
      (node (ref "ISA") (pin "D12") (pinfunction "~{DACK6}_D12") (pintype "output"))
      (node (ref "U11") (pin "27") (pinfunction "2A7_27") (pintype "bidirectional"))
    )
    (net (code "252") (name "~{DACK7}") (class "Default")
      (node (ref "ISA") (pin "D14") (pinfunction "~{DACK7}_D14") (pintype "output"))
      (node (ref "U11") (pin "26") (pinfunction "2A8_26") (pintype "bidirectional"))
    )
    (net (code "253") (name "~{IOR}") (class "Default")
      (node (ref "ISA") (pin "B14") (pinfunction "~{IOR}_B14") (pintype "bidirectional"))
      (node (ref "U11") (pin "43") (pinfunction "1A4_43") (pintype "bidirectional"))
    )
    (net (code "254") (name "~{IOW}") (class "Default")
      (node (ref "ISA") (pin "B13") (pinfunction "~{IOW}_B13") (pintype "bidirectional"))
      (node (ref "U11") (pin "44") (pinfunction "1A3_44") (pintype "bidirectional"))
    )
    (net (code "255") (name "~{MASTER}") (class "Default")
      (node (ref "IC1") (pin "8") (pinfunction "O_8") (pintype "open_collector"))
      (node (ref "ISA") (pin "D17") (pinfunction "~{MASTER}_D17") (pintype "input"))
    )
    (net (code "256") (name "~{MEMCS16}") (class "Default")
      (node (ref "IC1") (pin "10") (pinfunction "O_10") (pintype "open_collector"))
      (node (ref "ISA") (pin "D1") (pinfunction "~{MEMCS16}_D1") (pintype "input"))
    )
    (net (code "257") (name "~{MEMR}") (class "Default")
      (node (ref "ISA") (pin "C9") (pinfunction "~{MEMR}_C9") (pintype "bidirectional"))
      (node (ref "U11") (pin "47") (pinfunction "1A1_47") (pintype "bidirectional"))
    )
    (net (code "258") (name "~{MEMW}") (class "Default")
      (node (ref "ISA") (pin "C10") (pinfunction "~{MEMW}_C10") (pintype "bidirectional"))
      (node (ref "U11") (pin "46") (pinfunction "1A2_46") (pintype "bidirectional"))
    )
    (net (code "259") (name "~{REFRESH}") (class "Default")
      (node (ref "IC1") (pin "12") (pinfunction "O_12") (pintype "open_collector"))
      (node (ref "ISA") (pin "B19") (pinfunction "~{REFRESH}_B19") (pintype "bidirectional"))
    )
    (net (code "260") (name "~{SMEMR}") (class "Default")
      (node (ref "ISA") (pin "B12") (pinfunction "~{SMEMR}_B12") (pintype "output"))
      (node (ref "U10") (pin "26") (pinfunction "2A8_26") (pintype "bidirectional"))
    )
    (net (code "261") (name "~{SMEMW}") (class "Default")
      (node (ref "ISA") (pin "B11") (pinfunction "~{SMEMW}_B11") (pintype "output"))
      (node (ref "U10") (pin "27") (pinfunction "2A7_27") (pintype "bidirectional"))
    )
  )
)
